# v1-1-0c.net
KiCad netlist of a schematic drawn in EAGLE
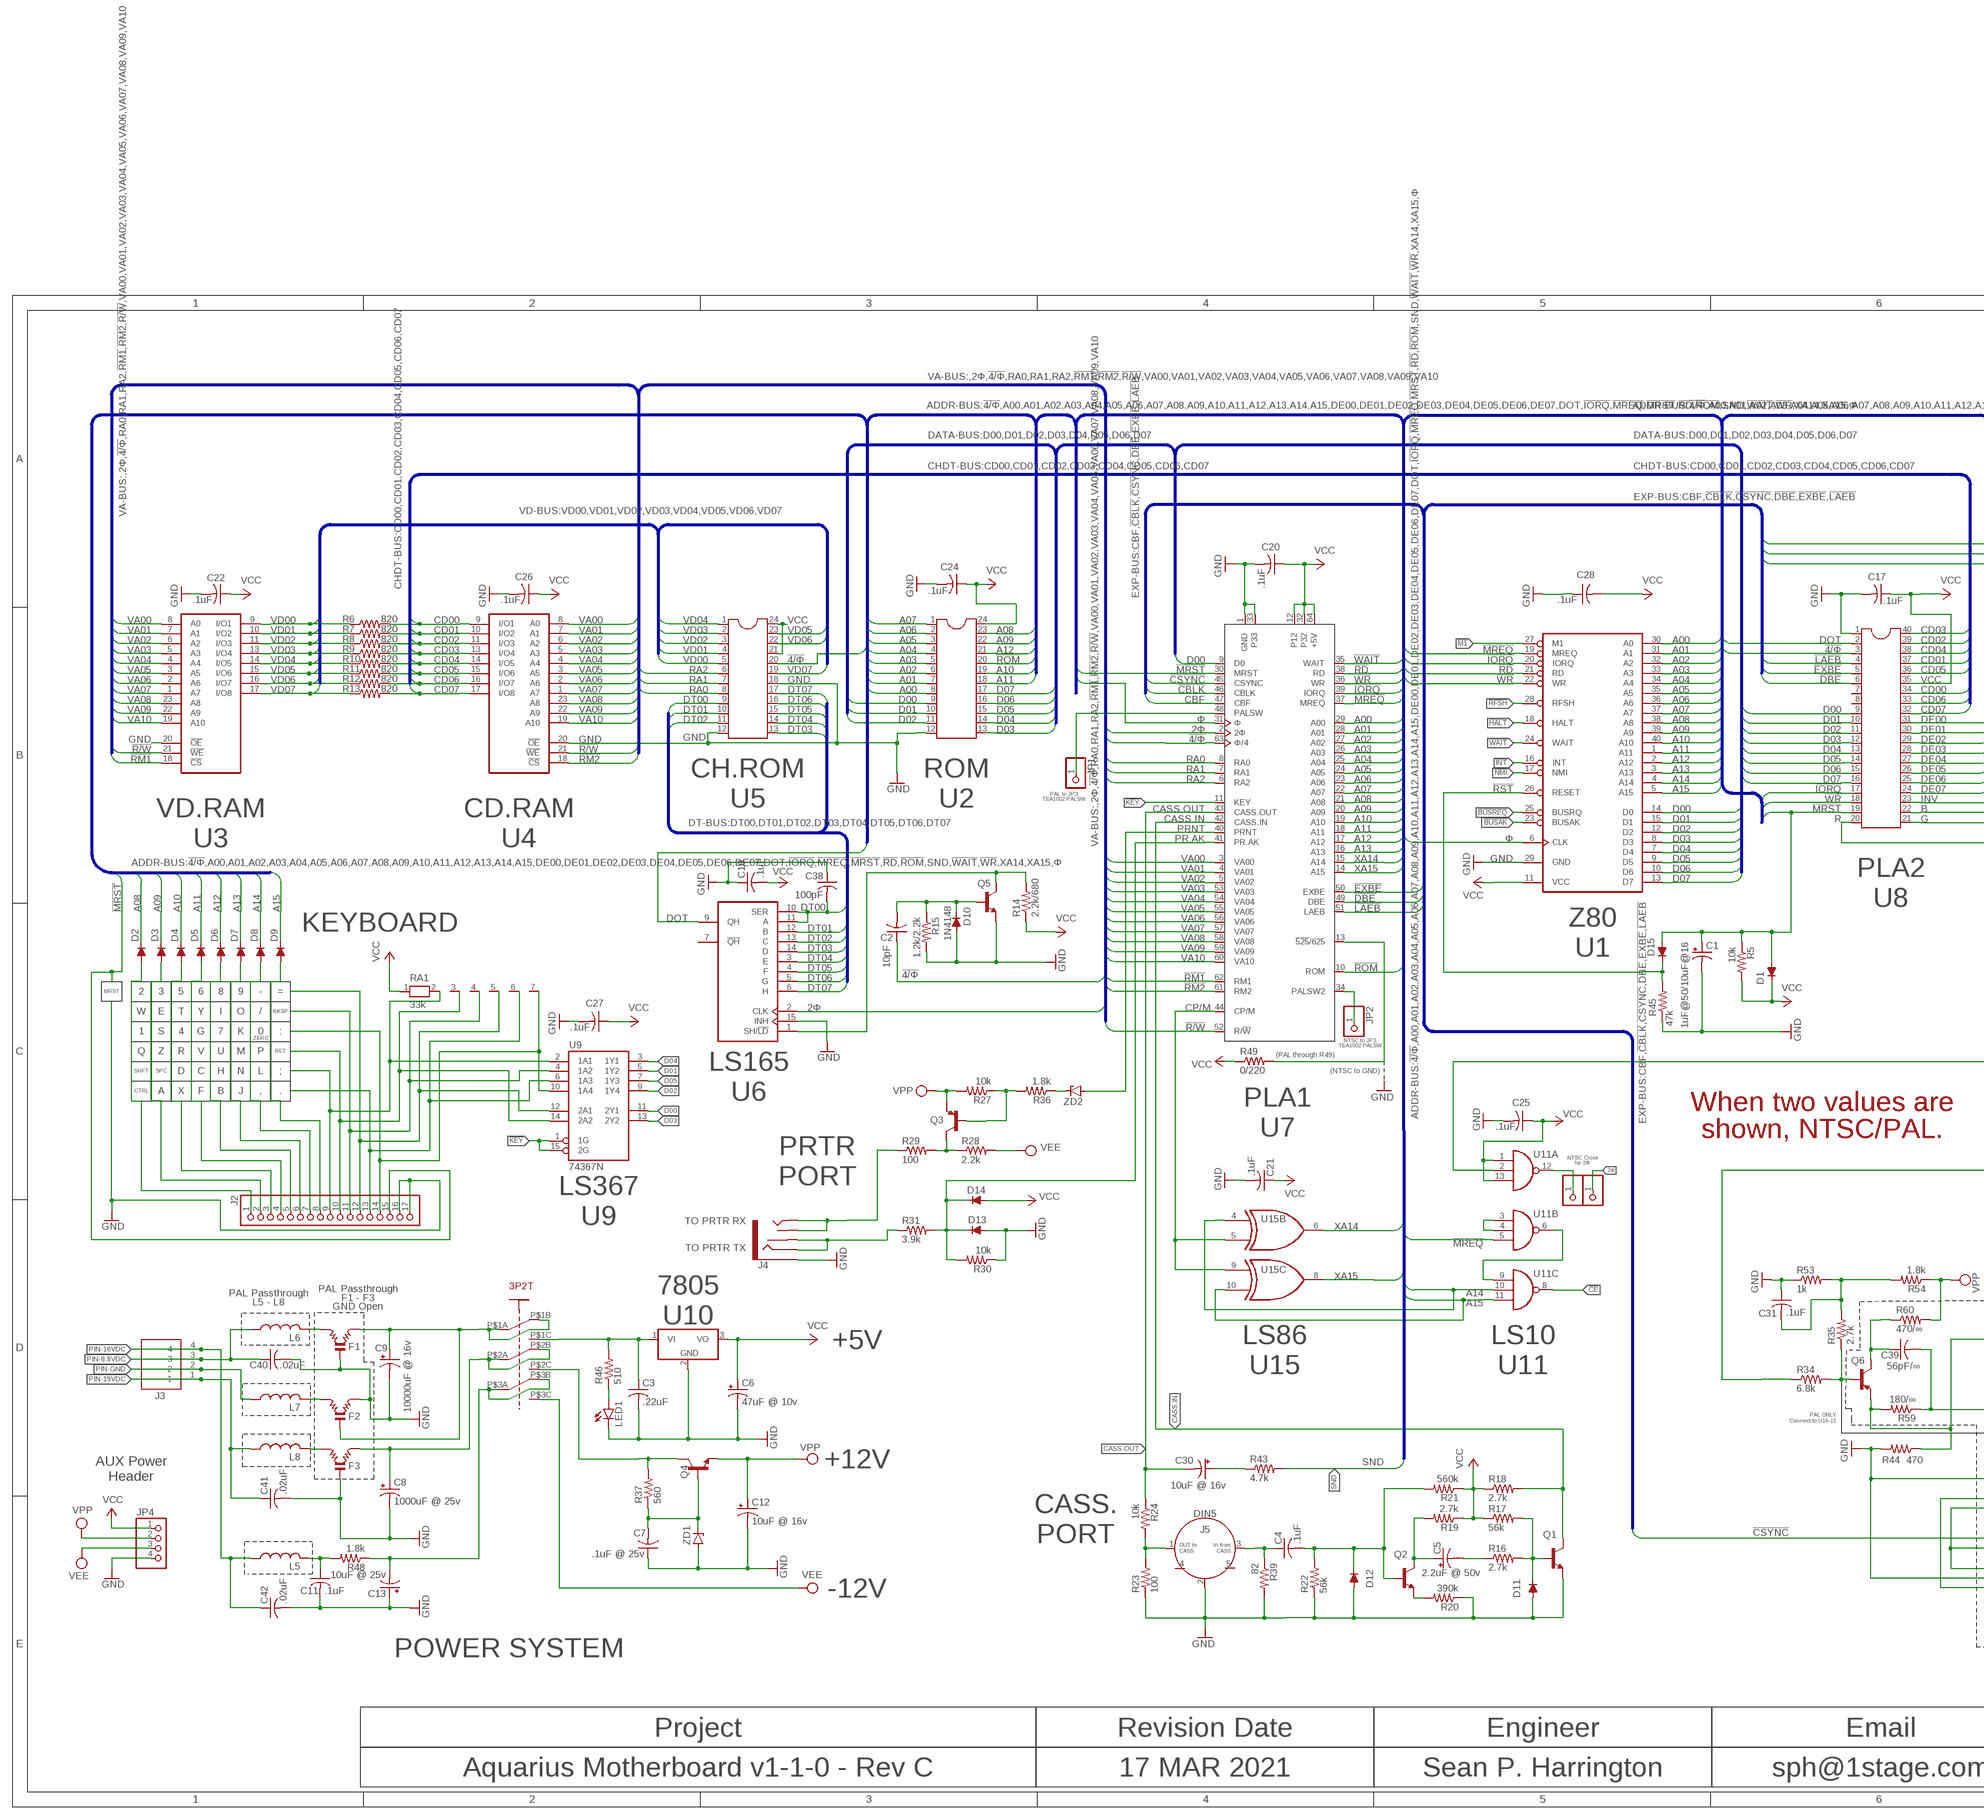
[diagram p0: schematic, sheet 1, part 1 of 2]
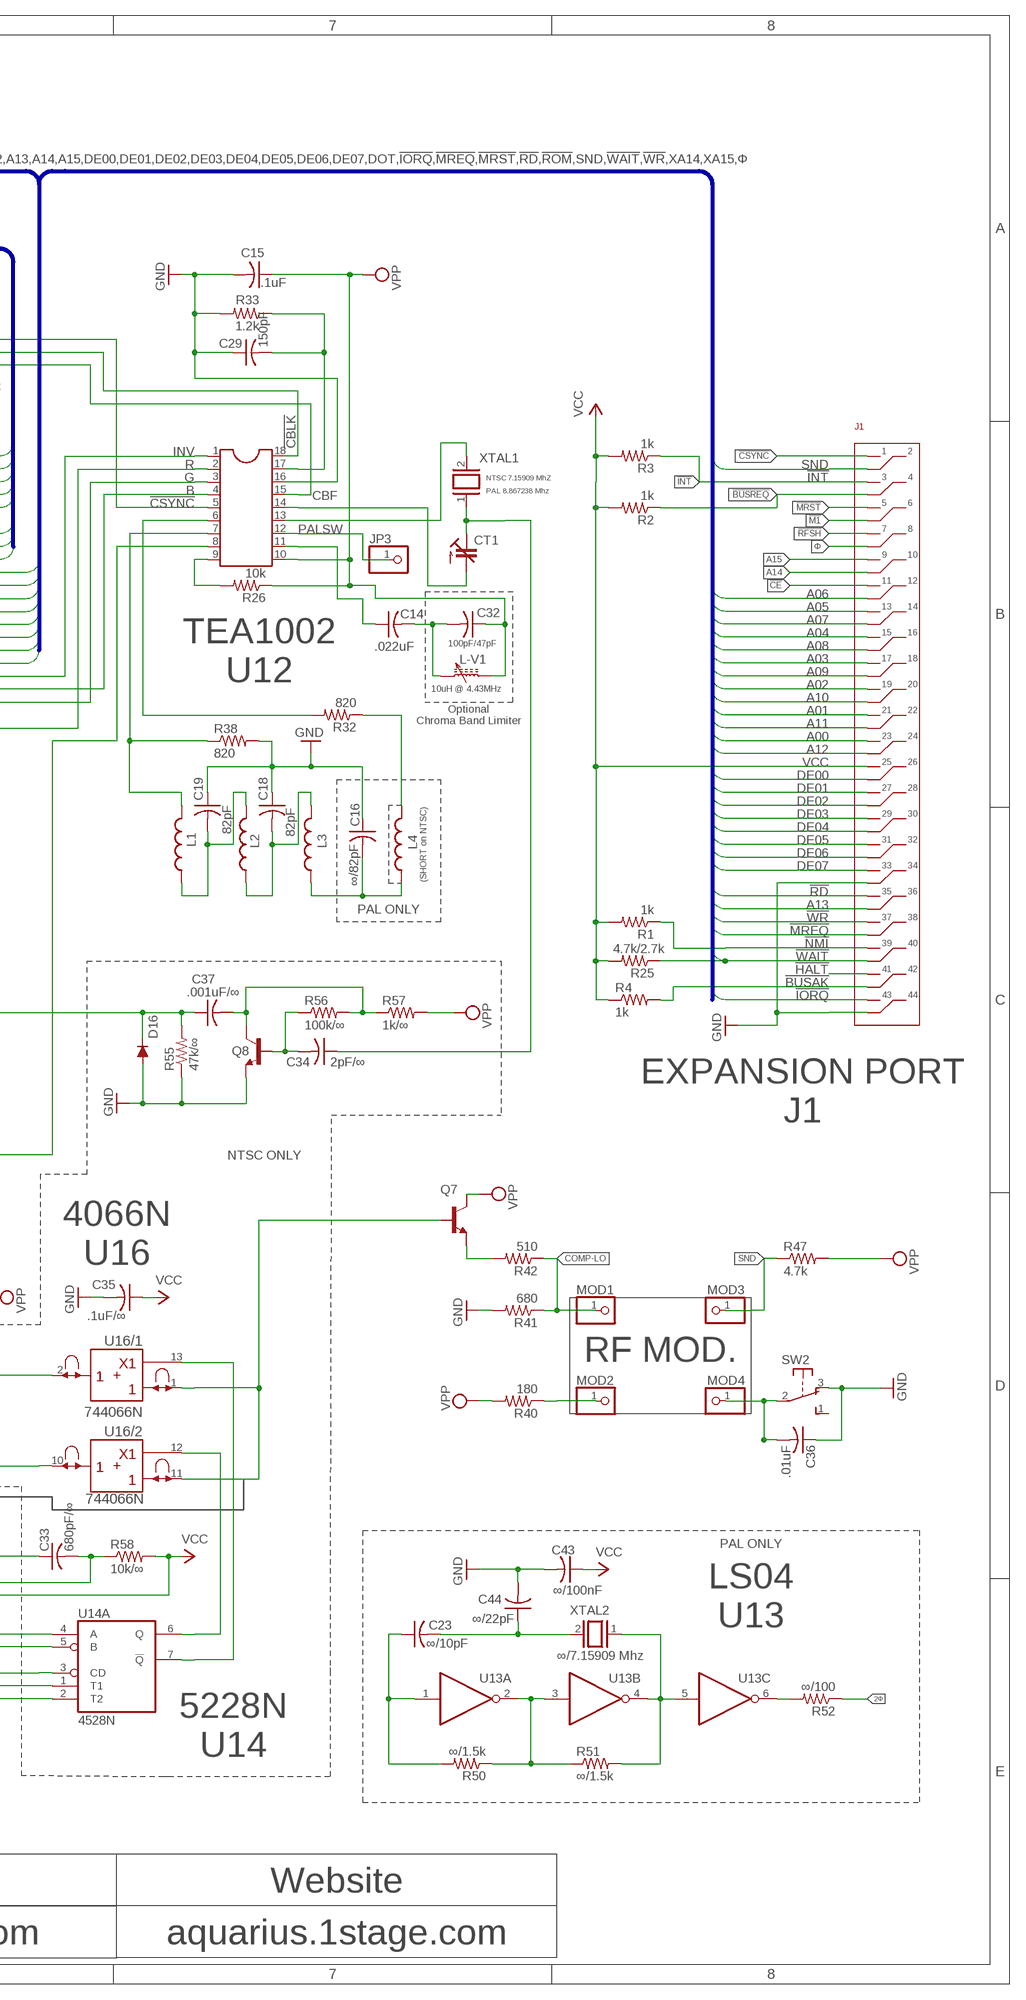
[diagram p1: schematic, sheet 1, part 2 of 2]

(export (version "E")
  (design (tool "Eeschema 10.0.6"))
  (components
    (comp (ref "C1")
      (value "1uF@50/10uF@16")
      (footprint "eagle-import:E2,5-6")
      (libsource (lib "eagle-import") (part "CPOL-USE2.5-6"))
    )
    (comp (ref "C2")
      (value "10pF")
      (footprint "eagle-import:C050-024X044")
      (libsource (lib "eagle-import") (part "C-US050-024X044"))
    )
    (comp (ref "C3")
      (value ".22uF")
      (footprint "eagle-import:C050-025X090")
      (libsource (lib "eagle-import") (part "C-US050-025X090"))
    )
    (comp (ref "C4")
      (value ".1uF")
      (footprint "eagle-import:C050-025X090")
      (libsource (lib "eagle-import") (part "C-US050-025X090"))
    )
    (comp (ref "C5")
      (value "2.2uF @ 50v")
      (footprint "eagle-import:E2,5-6")
      (libsource (lib "eagle-import") (part "CPOL-USE2.5-6"))
    )
    (comp (ref "C6")
      (value "47uF @ 10v")
      (footprint "eagle-import:E2,5-6")
      (libsource (lib "eagle-import") (part "CPOL-USE2.5-6"))
    )
    (comp (ref "C7")
      (value ".1uF @ 25v")
      (footprint "eagle-import:C050-025X090")
      (libsource (lib "eagle-import") (part "C-US050-025X090"))
    )
    (comp (ref "C8")
      (value "1000uF @ 25v")
      (footprint "eagle-import:E7,5-16")
      (libsource (lib "eagle-import") (part "CPOL-USE7.5-16"))
    )
    (comp (ref "C9")
      (value "10000uF @ 16v")
      (footprint "eagle-import:E45-18")
      (libsource (lib "eagle-import") (part "CPOL-USE45-18AXIAL"))
    )
    (comp (ref "C10")
      (value ".1uF")
      (footprint "eagle-import:C050-025X090")
      (libsource (lib "eagle-import") (part "C-US050-025X090"))
    )
    (comp (ref "C11")
      (value ".1uF")
      (footprint "eagle-import:C050-025X090")
      (libsource (lib "eagle-import") (part "C-US050-025X090"))
    )
    (comp (ref "C12")
      (value "10uF @ 16v")
      (footprint "eagle-import:E2,5-6")
      (libsource (lib "eagle-import") (part "CPOL-USE2.5-6"))
    )
    (comp (ref "C13")
      (value "10uF @ 25v")
      (footprint "eagle-import:E2,5-6")
      (libsource (lib "eagle-import") (part "CPOL-USE2.5-6"))
    )
    (comp (ref "C14")
      (value ".022uF")
      (footprint "eagle-import:C050-024X044")
      (libsource (lib "eagle-import") (part "C-US050-024X044"))
    )
    (comp (ref "C15")
      (value ".1uF")
      (footprint "eagle-import:C050-025X090")
      (libsource (lib "eagle-import") (part "C-US050-025X090"))
    )
    (comp (ref "C16")
      (value "∞/82pF")
      (footprint "eagle-import:C050-024X044")
      (libsource (lib "eagle-import") (part "C-US050-024X044"))
    )
    (comp (ref "C17")
      (value ".1uF")
      (footprint "eagle-import:C050-025X090")
      (libsource (lib "eagle-import") (part "C-US050-025X090"))
    )
    (comp (ref "C18")
      (value "82pF")
      (footprint "eagle-import:C050-024X044")
      (libsource (lib "eagle-import") (part "C-US050-024X044"))
    )
    (comp (ref "C19")
      (value "82pF")
      (footprint "eagle-import:C050-024X044")
      (libsource (lib "eagle-import") (part "C-US050-024X044"))
    )
    (comp (ref "C20")
      (value ".1uF")
      (footprint "eagle-import:C050-025X090")
      (libsource (lib "eagle-import") (part "C-US050-025X090"))
    )
    (comp (ref "C21")
      (value ".1uF")
      (footprint "eagle-import:C050-025X090")
      (libsource (lib "eagle-import") (part "C-US050-025X090"))
    )
    (comp (ref "C22")
      (value ".1uF")
      (footprint "eagle-import:C050-025X085")
      (libsource (lib "eagle-import") (part "C-US050-025X085"))
    )
    (comp (ref "C23")
      (value "∞/10pF")
      (footprint "eagle-import:C050-024X044")
      (libsource (lib "eagle-import") (part "C-US050-024X044"))
    )
    (comp (ref "C24")
      (value ".1uF")
      (footprint "eagle-import:C050-025X090")
      (libsource (lib "eagle-import") (part "C-US050-025X090"))
    )
    (comp (ref "C25")
      (value ".1uF")
      (footprint "eagle-import:C050-025X090")
      (libsource (lib "eagle-import") (part "C-US050-025X090"))
    )
    (comp (ref "C26")
      (value ".1uF")
      (footprint "eagle-import:C050-025X085")
      (libsource (lib "eagle-import") (part "C-US050-025X085"))
    )
    (comp (ref "C27")
      (value ".1uF")
      (footprint "eagle-import:C050-025X090")
      (libsource (lib "eagle-import") (part "C-US050-025X090"))
    )
    (comp (ref "C28")
      (value ".1uF")
      (footprint "eagle-import:C050-025X090")
      (libsource (lib "eagle-import") (part "C-US050-025X090"))
    )
    (comp (ref "C29")
      (value "150pF")
      (footprint "eagle-import:C050-024X044")
      (libsource (lib "eagle-import") (part "C-US050-024X044"))
    )
    (comp (ref "C30")
      (value "10uF @ 16v")
      (footprint "eagle-import:E2,5-6")
      (libsource (lib "eagle-import") (part "CPOL-USE2.5-6"))
    )
    (comp (ref "C31")
      (value ".1uF")
      (footprint "eagle-import:C050-024X044")
      (libsource (lib "eagle-import") (part "C-US050-024X044"))
    )
    (comp (ref "C32")
      (value "100pF/47pF")
      (footprint "eagle-import:C025-024X044")
      (libsource (lib "eagle-import") (part "C-US025-024X044"))
    )
    (comp (ref "C33")
      (value "680pF/∞")
      (footprint "eagle-import:C050-024X044")
      (libsource (lib "eagle-import") (part "C-US050-024X044"))
    )
    (comp (ref "C34")
      (value "2pF/∞")
      (footprint "eagle-import:C025-024X044")
      (libsource (lib "eagle-import") (part "C-US025-024X044"))
    )
    (comp (ref "C35")
      (value ".1uF/∞")
      (footprint "eagle-import:C050-025X090")
      (libsource (lib "eagle-import") (part "C-US050-025X090"))
    )
    (comp (ref "C36")
      (value ".01uF")
      (footprint "eagle-import:C050-024X044")
      (libsource (lib "eagle-import") (part "C-US050-024X044"))
    )
    (comp (ref "C37")
      (value ".001uF/∞")
      (footprint "eagle-import:C025-030X050")
      (libsource (lib "eagle-import") (part "C-US025-030X050"))
    )
    (comp (ref "C38")
      (value "100pF")
      (footprint "eagle-import:C050-025X085")
      (libsource (lib "eagle-import") (part "C-US050-025X085"))
    )
    (comp (ref "C39")
      (value "56pF/∞")
      (footprint "eagle-import:C050-024X044")
      (libsource (lib "eagle-import") (part "C-US050-024X044"))
    )
    (comp (ref "C40")
      (value ".02uF")
      (footprint "eagle-import:C050-025X090")
      (libsource (lib "eagle-import") (part "C-US050-025X090"))
    )
    (comp (ref "C41")
      (value ".02uF")
      (footprint "eagle-import:C050-025X090")
      (libsource (lib "eagle-import") (part "C-US050-025X090"))
    )
    (comp (ref "C42")
      (value ".02uF")
      (footprint "eagle-import:C050-025X090")
      (libsource (lib "eagle-import") (part "C-US050-025X090"))
    )
    (comp (ref "C43")
      (value "∞/100nF")
      (footprint "eagle-import:C050-025X090")
      (libsource (lib "eagle-import") (part "C-US050-025X090"))
    )
    (comp (ref "C44")
      (value "∞/22pF")
      (footprint "eagle-import:C050-024X044")
      (libsource (lib "eagle-import") (part "C-US050-024X044"))
    )
    (comp (ref "CT1")
      (value "C-TRIMM808")
      (footprint "eagle-import:CTRIM808-BC")
      (libsource (lib "eagle-import") (part "C-TRIMM808"))
    )
    (comp (ref "D1")
      (value "1N4148")
      (footprint "eagle-import:DO35-10")
      (libsource (lib "eagle-import") (part "1N4148"))
    )
    (comp (ref "D2")
      (value "1N4148H")
      (footprint "eagle-import:DO35-12")
      (libsource (lib "eagle-import") (part "1N4148-12"))
    )
    (comp (ref "D3")
      (value "1N4148H")
      (footprint "eagle-import:DO35-12")
      (libsource (lib "eagle-import") (part "1N4148-12"))
    )
    (comp (ref "D4")
      (value "1N4148H")
      (footprint "eagle-import:DO35-12")
      (libsource (lib "eagle-import") (part "1N4148-12"))
    )
    (comp (ref "D5")
      (value "1N4148H")
      (footprint "eagle-import:DO35-12")
      (libsource (lib "eagle-import") (part "1N4148-12"))
    )
    (comp (ref "D6")
      (value "1N4148H")
      (footprint "eagle-import:DO35-12")
      (libsource (lib "eagle-import") (part "1N4148-12"))
    )
    (comp (ref "D7")
      (value "1N4148H")
      (footprint "eagle-import:DO35-12")
      (libsource (lib "eagle-import") (part "1N4148-12"))
    )
    (comp (ref "D8")
      (value "1N4148H")
      (footprint "eagle-import:DO35-12")
      (libsource (lib "eagle-import") (part "1N4148-12"))
    )
    (comp (ref "D9")
      (value "1N4148H")
      (footprint "eagle-import:DO35-12")
      (libsource (lib "eagle-import") (part "1N4148-12"))
    )
    (comp (ref "D10")
      (value "1N4148")
      (footprint "eagle-import:DO35-10")
      (libsource (lib "eagle-import") (part "1N4148"))
    )
    (comp (ref "D11")
      (value "1N4148")
      (footprint "eagle-import:DO35-10")
      (libsource (lib "eagle-import") (part "1N4148"))
    )
    (comp (ref "D12")
      (value "1N4148")
      (footprint "eagle-import:DO35-10")
      (libsource (lib "eagle-import") (part "1N4148"))
    )
    (comp (ref "D13")
      (value "1N4148")
      (footprint "eagle-import:DO35-10")
      (libsource (lib "eagle-import") (part "1N4148"))
    )
    (comp (ref "D14")
      (value "1N4148")
      (footprint "eagle-import:DO35-10")
      (libsource (lib "eagle-import") (part "1N4148"))
    )
    (comp (ref "D15")
      (value "1N4148")
      (footprint "eagle-import:DO35-10")
      (libsource (lib "eagle-import") (part "1N4148"))
    )
    (comp (ref "D16")
      (value "1N4148")
      (footprint "eagle-import:DO35-10")
      (libsource (lib "eagle-import") (part "1N4148"))
    )
    (comp (ref "F1")
      (value "LCL")
      (footprint "eagle-import:LCL")
      (libsource (lib "eagle-import") (part "LCL"))
    )
    (comp (ref "F2")
      (value "LCL")
      (footprint "eagle-import:LCL")
      (libsource (lib "eagle-import") (part "LCL"))
    )
    (comp (ref "F3")
      (value "LCL")
      (footprint "eagle-import:LCL")
      (libsource (lib "eagle-import") (part "LCL"))
    )
    (comp (ref "J1")
      (value "CR22A-44D-2.54DSA(70)")
      (footprint "eagle-import:CR22A-44D-2.54DSA(70)")
      (libsource (lib "eagle-import") (part "CR22A-44D-2.54DSA(70)"))
    )
    (comp (ref "J2")
      (value "PINHD-1X17")
      (footprint "eagle-import:1X17")
      (libsource (lib "eagle-import") (part "PINHD-1X17"))
    )
    (comp (ref "J3")
      (value "26-60-4040")
      (footprint "eagle-import:SHDR4W155P0X396_1X4_1570X1001X")
      (fields (field (name "MOUSER_PART_NUMBER") "538-26-60-4040"))
      (libsource (lib "eagle-import") (part "26-60-4040"))
    )
    (comp (ref "J4")
      (value "AUDIO_JACK_3.5MM_PTH")
      (footprint "eagle-import:AUDIO-JACK")
      (libsource (lib "eagle-import") (part "AUDIO_JACK_3.5MM_PTH"))
    )
    (comp (ref "J5")
      (value "DIN5")
      (footprint "eagle-import:DIN5-RA-PTH")
      (libsource (lib "eagle-import") (part "DIN5"))
    )
    (comp (ref "JP1")
      (value "PINHD-1X1")
      (footprint "eagle-import:1X01")
      (libsource (lib "eagle-import") (part "PINHD-1X1"))
    )
    (comp (ref "JP2")
      (value "PINHD-1X1")
      (footprint "eagle-import:1X01")
      (libsource (lib "eagle-import") (part "PINHD-1X1"))
    )
    (comp (ref "JP3")
      (value "PINHD-1X1")
      (footprint "eagle-import:1X01")
      (libsource (lib "eagle-import") (part "PINHD-1X1"))
    )
    (comp (ref "JP4")
      (value "PINHD-1X4")
      (footprint "eagle-import:1X04")
      (libsource (lib "eagle-import") (part "PINHD-1X4"))
    )
    (comp (ref "JP5")
      (value "PINHD-1X1")
      (footprint "eagle-import:1X01")
      (libsource (lib "eagle-import") (part "PINHD-1X1"))
    )
    (comp (ref "JP6")
      (value "PINHD-1X1")
      (footprint "eagle-import:1X01")
      (libsource (lib "eagle-import") (part "PINHD-1X1"))
    )
    (comp (ref "L-V1")
      (value "10uH @ 4.43MHz")
      (footprint "eagle-import:10MM-VAR-IND")
      (libsource (lib "eagle-import") (part "L-VAR-IND"))
    )
    (comp (ref "L1")
      (value "L-USTFI0305")
      (footprint "eagle-import:TFI0305")
      (libsource (lib "eagle-import") (part "L-USTFI0305"))
    )
    (comp (ref "L2")
      (value "L-USTFI0305")
      (footprint "eagle-import:TFI0305")
      (libsource (lib "eagle-import") (part "L-USTFI0305"))
    )
    (comp (ref "L3")
      (value "L-USTFI0305")
      (footprint "eagle-import:TFI0305")
      (libsource (lib "eagle-import") (part "L-USTFI0305"))
    )
    (comp (ref "L4")
      (value "L-USTFI0305")
      (footprint "eagle-import:TFI0305")
      (libsource (lib "eagle-import") (part "L-USTFI0305"))
    )
    (comp (ref "L5")
      (value "L-USTFI0305")
      (footprint "eagle-import:TFI0305")
      (libsource (lib "eagle-import") (part "L-USTFI0305"))
    )
    (comp (ref "L6")
      (value "L-USTFI0305")
      (footprint "eagle-import:TFI0305")
      (libsource (lib "eagle-import") (part "L-USTFI0305"))
    )
    (comp (ref "L7")
      (value "L-USTFI0305")
      (footprint "eagle-import:TFI0305")
      (libsource (lib "eagle-import") (part "L-USTFI0305"))
    )
    (comp (ref "L8")
      (value "L-USTFI0305")
      (footprint "eagle-import:TFI0305")
      (libsource (lib "eagle-import") (part "L-USTFI0305"))
    )
    (comp (ref "LED1")
      (value "LED5MM")
      (footprint "eagle-import:LED5MM")
      (libsource (lib "eagle-import") (part "LED5MM"))
    )
    (comp (ref "MOD1")
      (value "PINHD-1X1")
      (footprint "eagle-import:1X01")
      (libsource (lib "eagle-import") (part "PINHD-1X1"))
    )
    (comp (ref "MOD2")
      (value "PINHD-1X1")
      (footprint "eagle-import:1X01")
      (libsource (lib "eagle-import") (part "PINHD-1X1"))
    )
    (comp (ref "MOD3")
      (value "PINHD-1X1")
      (footprint "eagle-import:1X01")
      (libsource (lib "eagle-import") (part "PINHD-1X1"))
    )
    (comp (ref "MOD4")
      (value "PINHD-1X1")
      (footprint "eagle-import:1X01")
      (libsource (lib "eagle-import") (part "PINHD-1X1"))
    )
    (comp (ref "Q1")
      (value "-NPN-TO92-E1")
      (footprint "eagle-import:TO92-E1")
      (libsource (lib "eagle-import") (part "-NPN-TO92-E1"))
    )
    (comp (ref "Q2")
      (value "-NPN-TO92-E1")
      (footprint "eagle-import:TO92-E1")
      (libsource (lib "eagle-import") (part "-NPN-TO92-E1"))
    )
    (comp (ref "Q3")
      (value "-PNP-TO92-E1")
      (footprint "eagle-import:TO92-E1")
      (libsource (lib "eagle-import") (part "-PNP-TO92-E1"))
    )
    (comp (ref "Q4")
      (value "-NPN-TO220V")
      (footprint "eagle-import:TO220V")
      (libsource (lib "eagle-import") (part "transistor_402_-NPN-TO220V"))
    )
    (comp (ref "Q5")
      (value "-NPN-TO92-E1")
      (footprint "eagle-import:TO92-E1")
      (libsource (lib "eagle-import") (part "-NPN-TO92-E1"))
    )
    (comp (ref "Q6")
      (value "-PNP-TO92-E1")
      (footprint "eagle-import:TO92-E1")
      (libsource (lib "eagle-import") (part "-PNP-TO92-E1"))
    )
    (comp (ref "Q7")
      (value "-NPN-TO92-E1")
      (footprint "eagle-import:TO92-E1")
      (libsource (lib "eagle-import") (part "-NPN-TO92-E1"))
    )
    (comp (ref "Q8")
      (value "-NPN-TO92-E1")
      (footprint "eagle-import:TO92-E1")
      (libsource (lib "eagle-import") (part "-NPN-TO92-E1"))
    )
    (comp (ref "R1")
      (value "1k")
      (footprint "eagle-import:0207_10")
      (libsource (lib "eagle-import") (part "R-US_0207/10"))
    )
    (comp (ref "R2")
      (value "1k")
      (footprint "eagle-import:0207_10")
      (libsource (lib "eagle-import") (part "R-US_0207/10"))
    )
    (comp (ref "R3")
      (value "1k")
      (footprint "eagle-import:0207_10")
      (libsource (lib "eagle-import") (part "R-US_0207/10"))
    )
    (comp (ref "R4")
      (value "1k")
      (footprint "eagle-import:0207_10")
      (libsource (lib "eagle-import") (part "R-US_0207/10"))
    )
    (comp (ref "R5")
      (value "10k")
      (footprint "eagle-import:0207_10")
      (libsource (lib "eagle-import") (part "R-US_0207/10"))
    )
    (comp (ref "R6")
      (value "820")
      (footprint "eagle-import:0207_10")
      (libsource (lib "eagle-import") (part "R-US_0207/10"))
    )
    (comp (ref "R7")
      (value "820")
      (footprint "eagle-import:0207_10")
      (libsource (lib "eagle-import") (part "R-US_0207/10"))
    )
    (comp (ref "R8")
      (value "820")
      (footprint "eagle-import:0207_10")
      (libsource (lib "eagle-import") (part "R-US_0207/10"))
    )
    (comp (ref "R9")
      (value "820")
      (footprint "eagle-import:0207_10")
      (libsource (lib "eagle-import") (part "R-US_0207/10"))
    )
    (comp (ref "R10")
      (value "820")
      (footprint "eagle-import:0207_10")
      (libsource (lib "eagle-import") (part "R-US_0207/10"))
    )
    (comp (ref "R11")
      (value "820")
      (footprint "eagle-import:0207_10")
      (libsource (lib "eagle-import") (part "R-US_0207/10"))
    )
    (comp (ref "R12")
      (value "820")
      (footprint "eagle-import:0207_10")
      (libsource (lib "eagle-import") (part "R-US_0207/10"))
    )
    (comp (ref "R13")
      (value "820")
      (footprint "eagle-import:0207_10")
      (libsource (lib "eagle-import") (part "R-US_0207/10"))
    )
    (comp (ref "R14")
      (value "2.2k/680")
      (footprint "eagle-import:0207_10")
      (libsource (lib "eagle-import") (part "R-US_0207/10"))
    )
    (comp (ref "R15")
      (value "1.2k/2.2k")
      (footprint "eagle-import:0207_10")
      (libsource (lib "eagle-import") (part "R-US_0207/10"))
    )
    (comp (ref "R16")
      (value "2.7k")
      (footprint "eagle-import:0207_10")
      (libsource (lib "eagle-import") (part "R-US_0207/10"))
    )
    (comp (ref "R17")
      (value "56k")
      (footprint "eagle-import:0207_10")
      (libsource (lib "eagle-import") (part "R-US_0207/10"))
    )
    (comp (ref "R18")
      (value "2.7k")
      (footprint "eagle-import:0207_10")
      (libsource (lib "eagle-import") (part "R-US_0207/10"))
    )
    (comp (ref "R19")
      (value "2.7k")
      (footprint "eagle-import:0207_10")
      (libsource (lib "eagle-import") (part "R-US_0207/10"))
    )
    (comp (ref "R20")
      (value "390k")
      (footprint "eagle-import:0207_10")
      (libsource (lib "eagle-import") (part "R-US_0207/10"))
    )
    (comp (ref "R21")
      (value "560k")
      (footprint "eagle-import:0207_10")
      (libsource (lib "eagle-import") (part "R-US_0207/10"))
    )
    (comp (ref "R22")
      (value "56k")
      (footprint "eagle-import:0207_10")
      (libsource (lib "eagle-import") (part "R-US_0207/10"))
    )
    (comp (ref "R23")
      (value "100")
      (footprint "eagle-import:0207_10")
      (libsource (lib "eagle-import") (part "R-US_0207/10"))
    )
    (comp (ref "R24")
      (value "10k")
      (footprint "eagle-import:0207_10")
      (libsource (lib "eagle-import") (part "R-US_0207/10"))
    )
    (comp (ref "R25")
      (value "4.7k/2.7k")
      (footprint "eagle-import:0207_10")
      (libsource (lib "eagle-import") (part "R-US_0207/10"))
    )
    (comp (ref "R26")
      (value "10k")
      (footprint "eagle-import:0207_10")
      (libsource (lib "eagle-import") (part "R-US_0207/10"))
    )
    (comp (ref "R27")
      (value "10k")
      (footprint "eagle-import:0207_10")
      (libsource (lib "eagle-import") (part "R-US_0207/10"))
    )
    (comp (ref "R28")
      (value "2.2k")
      (footprint "eagle-import:0207_10")
      (libsource (lib "eagle-import") (part "R-US_0207/10"))
    )
    (comp (ref "R29")
      (value "100")
      (footprint "eagle-import:0207_10")
      (libsource (lib "eagle-import") (part "R-US_0207/10"))
    )
    (comp (ref "R30")
      (value "10k")
      (footprint "eagle-import:0207_10")
      (libsource (lib "eagle-import") (part "R-US_0207/10"))
    )
    (comp (ref "R31")
      (value "3.9k")
      (footprint "eagle-import:0207_10")
      (libsource (lib "eagle-import") (part "R-US_0207/10"))
    )
    (comp (ref "R32")
      (value "820")
      (footprint "eagle-import:0207_10")
      (libsource (lib "eagle-import") (part "R-US_0207/10"))
    )
    (comp (ref "R33")
      (value "1.2k")
      (footprint "eagle-import:0207_10")
      (libsource (lib "eagle-import") (part "R-US_0207/10"))
    )
    (comp (ref "R34")
      (value "6.8k")
      (footprint "eagle-import:0207_10")
      (libsource (lib "eagle-import") (part "R-US_0207/10"))
    )
    (comp (ref "R35")
      (value "2.7k")
      (footprint "eagle-import:0207_10")
      (libsource (lib "eagle-import") (part "R-US_0207/10"))
    )
    (comp (ref "R36")
      (value "1.8k")
      (footprint "eagle-import:0207_10")
      (libsource (lib "eagle-import") (part "R-US_0207/10"))
    )
    (comp (ref "R37")
      (value "560")
      (footprint "eagle-import:0207_10")
      (libsource (lib "eagle-import") (part "R-US_0207/10"))
    )
    (comp (ref "R38")
      (value "820")
      (footprint "eagle-import:0207_10")
      (libsource (lib "eagle-import") (part "R-US_0207/10"))
    )
    (comp (ref "R39")
      (value "82")
      (footprint "eagle-import:0207_10")
      (libsource (lib "eagle-import") (part "R-US_0207/10"))
    )
    (comp (ref "R40")
      (value "180")
      (footprint "eagle-import:0207_10")
      (libsource (lib "eagle-import") (part "R-US_0207/10"))
    )
    (comp (ref "R41")
      (value "680")
      (footprint "eagle-import:0207_10")
      (libsource (lib "eagle-import") (part "R-US_0207/10"))
    )
    (comp (ref "R42")
      (value "510")
      (footprint "eagle-import:0207_10")
      (libsource (lib "eagle-import") (part "R-US_0207/10"))
    )
    (comp (ref "R43")
      (value "4.7k")
      (footprint "eagle-import:0207_10")
      (libsource (lib "eagle-import") (part "R-US_0207/10"))
    )
    (comp (ref "R44")
      (value "470")
      (footprint "eagle-import:0207_10")
      (libsource (lib "eagle-import") (part "R-US_0207/10"))
    )
    (comp (ref "R45")
      (value "47k")
      (footprint "eagle-import:0207_10")
      (libsource (lib "eagle-import") (part "R-US_0207/10"))
    )
    (comp (ref "R46")
      (value "510")
      (footprint "eagle-import:0207_10")
      (libsource (lib "eagle-import") (part "R-US_0207/10"))
    )
    (comp (ref "R47")
      (value "4.7k")
      (footprint "eagle-import:0207_10")
      (libsource (lib "eagle-import") (part "R-US_0207/10"))
    )
    (comp (ref "R48")
      (value "1.8k")
      (footprint "eagle-import:0207_10")
      (libsource (lib "eagle-import") (part "R-US_0207/10"))
    )
    (comp (ref "R49")
      (value "0/220")
      (footprint "eagle-import:0207_10")
      (libsource (lib "eagle-import") (part "R-US_0207/10"))
    )
    (comp (ref "R50")
      (value "∞/1.5k")
      (footprint "eagle-import:0207_10")
      (libsource (lib "eagle-import") (part "R-US_0207/10"))
    )
    (comp (ref "R51")
      (value "∞/1.5k")
      (footprint "eagle-import:0207_10")
      (libsource (lib "eagle-import") (part "R-US_0207/10"))
    )
    (comp (ref "R52")
      (value "∞/100")
      (footprint "eagle-import:0207_10")
      (libsource (lib "eagle-import") (part "R-US_0207/10"))
    )
    (comp (ref "R53")
      (value "1k")
      (footprint "eagle-import:0207_10")
      (libsource (lib "eagle-import") (part "R-US_0207/10"))
    )
    (comp (ref "R54")
      (value "1.8k")
      (footprint "eagle-import:0207_10")
      (libsource (lib "eagle-import") (part "R-US_0207/10"))
    )
    (comp (ref "R55")
      (value "47k/∞")
      (footprint "eagle-import:0207_10")
      (libsource (lib "eagle-import") (part "R-US_0207/10"))
    )
    (comp (ref "R56")
      (value "100k/∞")
      (footprint "eagle-import:0207_10")
      (libsource (lib "eagle-import") (part "R-US_0207/10"))
    )
    (comp (ref "R57")
      (value "1k/∞")
      (footprint "eagle-import:0207_10")
      (libsource (lib "eagle-import") (part "R-US_0207/10"))
    )
    (comp (ref "R58")
      (value "10k/∞")
      (footprint "eagle-import:0207_10")
      (libsource (lib "eagle-import") (part "R-US_0207/10"))
    )
    (comp (ref "R59")
      (value "180/∞")
      (footprint "eagle-import:0207_10")
      (libsource (lib "eagle-import") (part "R-US_0207/10"))
    )
    (comp (ref "R60")
      (value "470/∞")
      (footprint "eagle-import:0207_10")
      (libsource (lib "eagle-import") (part "R-US_0207/10"))
    )
    (comp (ref "RA1")
      (value "33k")
      (footprint "eagle-import:RN-7")
      (libsource (lib "eagle-import") (part "RN06"))
    )
    (comp (ref "SW1")
      (value "3PDT-AQ-SWITCH")
      (footprint "eagle-import:3PDT-AQ-SWITCH")
      (libsource (lib "eagle-import") (part "3PDT-AQ-SWITCH"))
    )
    (comp (ref "SW2")
      (value "9077-1")
      (footprint "eagle-import:9077-1")
      (libsource (lib "eagle-import") (part "9077-1"))
    )
    (comp (ref "U1")
      (value "Z80CPU")
      (footprint "eagle-import:DIL40")
      (libsource (lib "eagle-import") (part "Z80CPU"))
    )
    (comp (ref "U2")
      (value "DIL24-6")
      (footprint "eagle-import:DIL24-6")
      (libsource (lib "eagle-import") (part "DIL24-6"))
    )
    (comp (ref "U3")
      (value "6116P")
      (footprint "eagle-import:DIL24-6")
      (libsource (lib "eagle-import") (part "6116P"))
    )
    (comp (ref "U4")
      (value "6116P")
      (footprint "eagle-import:DIL24-6")
      (libsource (lib "eagle-import") (part "6116P"))
    )
    (comp (ref "U5")
      (value "DIL24-6")
      (footprint "eagle-import:DIL24-6")
      (libsource (lib "eagle-import") (part "DIL24-6"))
    )
    (comp (ref "U6")
      (value "74LS165N")
      (footprint "eagle-import:DIL16")
      (libsource (lib "eagle-import") (part "74165NLS"))
    )
    (comp (ref "U7")
      (value "HD61K202P-PLA1")
      (footprint "eagle-import:HD61K202P-PLA1")
      (libsource (lib "eagle-import") (part "HD61K202P-PLA1"))
    )
    (comp (ref "U8")
      (value "DIL40")
      (footprint "eagle-import:DIL40")
      (libsource (lib "eagle-import") (part "DIL40"))
    )
    (comp (ref "U9")
      (value "74367N")
      (footprint "eagle-import:DIL16")
      (libsource (lib "eagle-import") (part "74367N"))
    )
    (comp (ref "U10")
      (value "7805")
      (footprint "eagle-import:TO220V")
      (libsource (lib "eagle-import") (part "78TV05"))
    )
    (comp (ref "U11")
      (value "74LS10N")
      (footprint "eagle-import:DIL14")
      (libsource (lib "eagle-import") (part "7410NLS"))
    )
    (comp (ref "U12")
      (value "DIL18")
      (footprint "eagle-import:DIL18")
      (libsource (lib "eagle-import") (part "DIL18"))
    )
    (comp (ref "U13")
      (value "74LS04N")
      (footprint "eagle-import:DIL14")
      (libsource (lib "eagle-import") (part "7404NLS"))
    )
    (comp (ref "U14")
      (value "4528N")
      (footprint "eagle-import:DIL16")
      (libsource (lib "eagle-import") (part "4528N"))
    )
    (comp (ref "U15")
      (value "74LS86N")
      (footprint "eagle-import:DIL14")
      (libsource (lib "eagle-import") (part "7486NLS"))
    )
    (comp (ref "U16")
      (value "744066N")
      (footprint "eagle-import:DIL14")
      (libsource (lib "eagle-import") (part "744066N"))
    )
    (comp (ref "XTAL1")
      (value "7.15909 MhZ")
      (footprint "eagle-import:Q")
      (libsource (lib "eagle-import") (part "special_367_XTAL"))
    )
    (comp (ref "XTAL2")
      (value "∞/7.15909 Mhz")
      (footprint "eagle-import:Q")
      (libsource (lib "eagle-import") (part "XTAL"))
    )
    (comp (ref "ZD1")
      (value "ZENER-DIODEZD-10")
      (footprint "eagle-import:ZDIO-10")
      (libsource (lib "eagle-import") (part "ZENER-DIODEZD-10"))
    )
    (comp (ref "ZD2")
      (value "ZENER-DIODEZD-7.5")
      (footprint "eagle-import:ZDIO-7.5")
      (libsource (lib "eagle-import") (part "ZENER-DIODEZD-7.5"))
    )
  )
  (nets
    (net (code "8") (name "/A00") (class "Default")
      (node (ref "J1") (pin "P$23") (pinfunction "X23_P$23") (pintype "bidirectional"))
      (node (ref "U1") (pin "30") (pinfunction "A0_30") (pintype "output"))
      (node (ref "U2") (pin "8") (pinfunction "8_8") (pintype "passive"))
      (node (ref "U7") (pin "29") (pinfunction "A00_29") (pintype "bidirectional"))
    )
    (net (code "9") (name "/A01") (class "Default")
      (node (ref "J1") (pin "P$21") (pinfunction "X21_P$21") (pintype "bidirectional"))
      (node (ref "U1") (pin "31") (pinfunction "A1_31") (pintype "output"))
      (node (ref "U2") (pin "7") (pinfunction "7_7") (pintype "passive"))
      (node (ref "U7") (pin "28") (pinfunction "A01_28") (pintype "bidirectional"))
    )
    (net (code "10") (name "/A02") (class "Default")
      (node (ref "J1") (pin "P$19") (pinfunction "X19_P$19") (pintype "bidirectional"))
      (node (ref "U1") (pin "32") (pinfunction "A2_32") (pintype "output"))
      (node (ref "U2") (pin "6") (pinfunction "6_6") (pintype "passive"))
      (node (ref "U7") (pin "27") (pinfunction "A02_27") (pintype "bidirectional"))
    )
    (net (code "11") (name "/A03") (class "Default")
      (node (ref "J1") (pin "P$17") (pinfunction "X17_P$17") (pintype "bidirectional"))
      (node (ref "U1") (pin "33") (pinfunction "A3_33") (pintype "output"))
      (node (ref "U2") (pin "5") (pinfunction "5_5") (pintype "passive"))
      (node (ref "U7") (pin "26") (pinfunction "A03_26") (pintype "bidirectional"))
    )
    (net (code "12") (name "/A04") (class "Default")
      (node (ref "J1") (pin "P$15") (pinfunction "X15_P$15") (pintype "bidirectional"))
      (node (ref "U1") (pin "34") (pinfunction "A4_34") (pintype "output"))
      (node (ref "U2") (pin "4") (pinfunction "4_4") (pintype "passive"))
      (node (ref "U7") (pin "25") (pinfunction "A04_25") (pintype "bidirectional"))
    )
    (net (code "13") (name "/A05") (class "Default")
      (node (ref "J1") (pin "P$13") (pinfunction "X13_P$13") (pintype "bidirectional"))
      (node (ref "U1") (pin "35") (pinfunction "A5_35") (pintype "output"))
      (node (ref "U2") (pin "3") (pinfunction "3_3") (pintype "passive"))
      (node (ref "U7") (pin "24") (pinfunction "A05_24") (pintype "bidirectional"))
    )
    (net (code "14") (name "/A06") (class "Default")
      (node (ref "J1") (pin "P$12") (pinfunction "X12_P$12") (pintype "bidirectional"))
      (node (ref "U1") (pin "36") (pinfunction "A6_36") (pintype "output"))
      (node (ref "U2") (pin "2") (pinfunction "2_2") (pintype "passive"))
      (node (ref "U7") (pin "23") (pinfunction "A06_23") (pintype "bidirectional"))
    )
    (net (code "15") (name "/A07") (class "Default")
      (node (ref "J1") (pin "P$14") (pinfunction "X14_P$14") (pintype "bidirectional"))
      (node (ref "U1") (pin "37") (pinfunction "A7_37") (pintype "output"))
      (node (ref "U2") (pin "1") (pinfunction "1_1") (pintype "passive"))
      (node (ref "U7") (pin "22") (pinfunction "A07_22") (pintype "bidirectional"))
    )
    (net (code "16") (name "/A08") (class "Default")
      (node (ref "D2") (pin "C") (pinfunction "C_C") (pintype "passive"))
      (node (ref "J1") (pin "P$16") (pinfunction "X16_P$16") (pintype "bidirectional"))
      (node (ref "U1") (pin "38") (pinfunction "A8_38") (pintype "output"))
      (node (ref "U2") (pin "23") (pinfunction "23_23") (pintype "passive"))
      (node (ref "U7") (pin "21") (pinfunction "A08_21") (pintype "bidirectional"))
    )
    (net (code "17") (name "/A09") (class "Default")
      (node (ref "D3") (pin "C") (pinfunction "C_C") (pintype "passive"))
      (node (ref "J1") (pin "P$18") (pinfunction "X18_P$18") (pintype "bidirectional"))
      (node (ref "U1") (pin "39") (pinfunction "A9_39") (pintype "output"))
      (node (ref "U2") (pin "22") (pinfunction "22_22") (pintype "passive"))
      (node (ref "U7") (pin "20") (pinfunction "A09_20") (pintype "bidirectional"))
    )
    (net (code "18") (name "/A10") (class "Default")
      (node (ref "D4") (pin "C") (pinfunction "C_C") (pintype "passive"))
      (node (ref "J1") (pin "P$20") (pinfunction "X20_P$20") (pintype "bidirectional"))
      (node (ref "U1") (pin "40") (pinfunction "A10_40") (pintype "output"))
      (node (ref "U2") (pin "19") (pinfunction "19_19") (pintype "passive"))
      (node (ref "U7") (pin "19") (pinfunction "A10_19") (pintype "bidirectional"))
    )
    (net (code "19") (name "/A11") (class "Default")
      (node (ref "D5") (pin "C") (pinfunction "C_C") (pintype "passive"))
      (node (ref "J1") (pin "P$22") (pinfunction "X22_P$22") (pintype "bidirectional"))
      (node (ref "U1") (pin "1") (pinfunction "A11_1") (pintype "output"))
      (node (ref "U2") (pin "18") (pinfunction "18_18") (pintype "passive"))
      (node (ref "U7") (pin "18") (pinfunction "A11_18") (pintype "bidirectional"))
    )
    (net (code "20") (name "/A12") (class "Default")
      (node (ref "D6") (pin "C") (pinfunction "C_C") (pintype "passive"))
      (node (ref "J1") (pin "P$24") (pinfunction "X24_P$24") (pintype "bidirectional"))
      (node (ref "U1") (pin "2") (pinfunction "A12_2") (pintype "output"))
      (node (ref "U2") (pin "21") (pinfunction "21_21") (pintype "passive"))
      (node (ref "U7") (pin "17") (pinfunction "A12_17") (pintype "bidirectional"))
    )
    (net (code "21") (name "/A13") (class "Default")
      (node (ref "D7") (pin "C") (pinfunction "C_C") (pintype "passive"))
      (node (ref "J1") (pin "P$36") (pinfunction "X36_P$36") (pintype "bidirectional"))
      (node (ref "U1") (pin "3") (pinfunction "A13_3") (pintype "output"))
      (node (ref "U7") (pin "16") (pinfunction "A13_16") (pintype "bidirectional"))
    )
    (net (code "22") (name "/B") (class "Default")
      (node (ref "U12") (pin "4") (pinfunction "4_4") (pintype "passive"))
      (node (ref "U8") (pin "22") (pinfunction "22_22") (pintype "passive"))
    )
    (net (code "23") (name "/CBF") (class "Default")
      (node (ref "U12") (pin "15") (pinfunction "15_15") (pintype "passive"))
      (node (ref "U7") (pin "47") (pinfunction "CBF_47") (pintype "bidirectional"))
    )
    (net (code "24") (name "/CD00") (class "Default")
      (node (ref "R6") (pin "2") (pinfunction "2_2") (pintype "passive"))
      (node (ref "U4") (pin "9") (pinfunction "I/O1_9") (pintype "bidirectional"))
      (node (ref "U8") (pin "34") (pinfunction "34_34") (pintype "passive"))
    )
    (net (code "25") (name "/CD01") (class "Default")
      (node (ref "R7") (pin "2") (pinfunction "2_2") (pintype "passive"))
      (node (ref "U4") (pin "10") (pinfunction "I/O2_10") (pintype "bidirectional"))
      (node (ref "U8") (pin "37") (pinfunction "37_37") (pintype "passive"))
    )
    (net (code "26") (name "/CD02") (class "Default")
      (node (ref "R8") (pin "2") (pinfunction "2_2") (pintype "passive"))
      (node (ref "U4") (pin "11") (pinfunction "I/O3_11") (pintype "bidirectional"))
      (node (ref "U8") (pin "39") (pinfunction "39_39") (pintype "passive"))
    )
    (net (code "27") (name "/CD03") (class "Default")
      (node (ref "R9") (pin "2") (pinfunction "2_2") (pintype "passive"))
      (node (ref "U4") (pin "13") (pinfunction "I/O4_13") (pintype "bidirectional"))
      (node (ref "U8") (pin "40") (pinfunction "40_40") (pintype "passive"))
    )
    (net (code "28") (name "/CD04") (class "Default")
      (node (ref "R10") (pin "2") (pinfunction "2_2") (pintype "passive"))
      (node (ref "U4") (pin "14") (pinfunction "I/O5_14") (pintype "bidirectional"))
      (node (ref "U8") (pin "38") (pinfunction "38_38") (pintype "passive"))
    )
    (net (code "29") (name "/CD05") (class "Default")
      (node (ref "R11") (pin "2") (pinfunction "2_2") (pintype "passive"))
      (node (ref "U4") (pin "15") (pinfunction "I/O6_15") (pintype "bidirectional"))
      (node (ref "U8") (pin "36") (pinfunction "36_36") (pintype "passive"))
    )
    (net (code "30") (name "/CD06") (class "Default")
      (node (ref "R12") (pin "2") (pinfunction "2_2") (pintype "passive"))
      (node (ref "U4") (pin "16") (pinfunction "I/O7_16") (pintype "bidirectional"))
      (node (ref "U8") (pin "33") (pinfunction "33_33") (pintype "passive"))
    )
    (net (code "31") (name "/CD07") (class "Default")
      (node (ref "R13") (pin "2") (pinfunction "2_2") (pintype "passive"))
      (node (ref "U4") (pin "17") (pinfunction "I/O8_17") (pintype "bidirectional"))
      (node (ref "U8") (pin "32") (pinfunction "32_32") (pintype "passive"))
    )
    (net (code "32") (name "/CP{slash}M") (class "Default")
      (node (ref "U15") (pin "5") (pinfunction "I1_5") (pintype "input"))
      (node (ref "U15") (pin "9") (pinfunction "I0_9") (pintype "input"))
      (node (ref "U7") (pin "44") (pinfunction "CP/M_44") (pintype "bidirectional"))
    )
    (net (code "33") (name "/D06") (class "Default")
      (node (ref "U1") (pin "10") (pinfunction "D6_10") (pintype "bidirectional"))
      (node (ref "U2") (pin "16") (pinfunction "16_16") (pintype "passive"))
      (node (ref "U8") (pin "15") (pinfunction "15_15") (pintype "passive"))
    )
    (net (code "34") (name "/D07") (class "Default")
      (node (ref "U1") (pin "13") (pinfunction "D7_13") (pintype "bidirectional"))
      (node (ref "U2") (pin "17") (pinfunction "17_17") (pintype "passive"))
      (node (ref "U8") (pin "16") (pinfunction "16_16") (pintype "passive"))
    )
    (net (code "35") (name "/DE00") (class "Default")
      (node (ref "J1") (pin "P$26") (pinfunction "X26_P$26") (pintype "bidirectional"))
      (node (ref "U8") (pin "31") (pinfunction "31_31") (pintype "passive"))
    )
    (net (code "36") (name "/DE01") (class "Default")
      (node (ref "J1") (pin "P$27") (pinfunction "X27_P$27") (pintype "bidirectional"))
      (node (ref "U8") (pin "30") (pinfunction "30_30") (pintype "passive"))
    )
    (net (code "37") (name "/DE02") (class "Default")
      (node (ref "J1") (pin "P$28") (pinfunction "X28_P$28") (pintype "bidirectional"))
      (node (ref "U8") (pin "29") (pinfunction "29_29") (pintype "passive"))
    )
    (net (code "38") (name "/DE03") (class "Default")
      (node (ref "J1") (pin "P$29") (pinfunction "X29_P$29") (pintype "bidirectional"))
      (node (ref "U8") (pin "28") (pinfunction "28_28") (pintype "passive"))
    )
    (net (code "39") (name "/DE04") (class "Default")
      (node (ref "J1") (pin "P$30") (pinfunction "X30_P$30") (pintype "bidirectional"))
      (node (ref "U8") (pin "27") (pinfunction "27_27") (pintype "passive"))
    )
    (net (code "40") (name "/DE05") (class "Default")
      (node (ref "J1") (pin "P$31") (pinfunction "X31_P$31") (pintype "bidirectional"))
      (node (ref "U8") (pin "26") (pinfunction "26_26") (pintype "passive"))
    )
    (net (code "41") (name "/DE06") (class "Default")
      (node (ref "J1") (pin "P$32") (pinfunction "X32_P$32") (pintype "bidirectional"))
      (node (ref "U8") (pin "25") (pinfunction "25_25") (pintype "passive"))
    )
    (net (code "42") (name "/DE07") (class "Default")
      (node (ref "J1") (pin "P$33") (pinfunction "X33_P$33") (pintype "bidirectional"))
      (node (ref "U8") (pin "24") (pinfunction "24_24") (pintype "passive"))
    )
    (net (code "43") (name "/DOT") (class "Default")
      (node (ref "U6") (pin "9") (pinfunction "QH_9") (pintype "output"))
      (node (ref "U8") (pin "2") (pinfunction "2_2") (pintype "passive"))
    )
    (net (code "44") (name "/DT00") (class "Default")
      (node (ref "C38") (pin "2") (pinfunction "2_2") (pintype "passive"))
      (node (ref "U5") (pin "9") (pinfunction "9_9") (pintype "passive"))
      (node (ref "U6") (pin "10") (pinfunction "SER_10") (pintype "input"))
      (node (ref "U6") (pin "11") (pinfunction "A_11") (pintype "input"))
    )
    (net (code "45") (name "/DT01") (class "Default")
      (node (ref "U5") (pin "10") (pinfunction "10_10") (pintype "passive"))
      (node (ref "U6") (pin "12") (pinfunction "B_12") (pintype "input"))
    )
    (net (code "46") (name "/DT02") (class "Default")
      (node (ref "U5") (pin "11") (pinfunction "11_11") (pintype "passive"))
      (node (ref "U6") (pin "13") (pinfunction "C_13") (pintype "input"))
    )
    (net (code "47") (name "/DT03") (class "Default")
      (node (ref "U5") (pin "13") (pinfunction "13_13") (pintype "passive"))
      (node (ref "U6") (pin "14") (pinfunction "D_14") (pintype "input"))
    )
    (net (code "48") (name "/DT04") (class "Default")
      (node (ref "U5") (pin "14") (pinfunction "14_14") (pintype "passive"))
      (node (ref "U6") (pin "3") (pinfunction "E_3") (pintype "input"))
    )
    (net (code "49") (name "/DT05") (class "Default")
      (node (ref "U5") (pin "15") (pinfunction "15_15") (pintype "passive"))
      (node (ref "U6") (pin "4") (pinfunction "F_4") (pintype "input"))
    )
    (net (code "50") (name "/DT06") (class "Default")
      (node (ref "U5") (pin "16") (pinfunction "16_16") (pintype "passive"))
      (node (ref "U6") (pin "5") (pinfunction "G_5") (pintype "input"))
    )
    (net (code "51") (name "/DT07") (class "Default")
      (node (ref "U5") (pin "17") (pinfunction "17_17") (pintype "passive"))
      (node (ref "U6") (pin "6") (pinfunction "H_6") (pintype "input"))
    )
    (net (code "52") (name "/G") (class "Default")
      (node (ref "U12") (pin "3") (pinfunction "3_3") (pintype "passive"))
      (node (ref "U8") (pin "21") (pinfunction "21_21") (pintype "passive"))
    )
    (net (code "53") (name "/INV") (class "Default")
      (node (ref "U12") (pin "1") (pinfunction "1_1") (pintype "passive"))
      (node (ref "U8") (pin "23") (pinfunction "23_23") (pintype "passive"))
    )
    (net (code "54") (name "/PALSW") (class "Default")
      (node (ref "JP3") (pin "1") (pinfunction "1_1") (pintype "passive"))
      (node (ref "U12") (pin "12") (pinfunction "12_12") (pintype "passive"))
    )
    (net (code "55") (name "/PR.AK") (class "Default")
      (node (ref "D13") (pin "C") (pinfunction "C_C") (pintype "passive"))
      (node (ref "D14") (pin "C") (pinfunction "C_C") (pintype "passive"))
      (node (ref "R30") (pin "2") (pinfunction "2_2") (pintype "passive"))
      (node (ref "R31") (pin "2") (pinfunction "2_2") (pintype "passive"))
      (node (ref "U7") (pin "41") (pinfunction "PR.AK_41") (pintype "bidirectional"))
    )
    (net (code "56") (name "/PRNT") (class "Default")
      (node (ref "U7") (pin "40") (pinfunction "PRNT_40") (pintype "bidirectional"))
      (node (ref "ZD2") (pin "A") (pinfunction "A_A") (pintype "passive"))
    )
    (net (code "57") (name "/R") (class "Default")
      (node (ref "U12") (pin "2") (pinfunction "2_2") (pintype "passive"))
      (node (ref "U8") (pin "20") (pinfunction "20_20") (pintype "passive"))
    )
    (net (code "58") (name "/RA0") (class "Default")
      (node (ref "U5") (pin "8") (pinfunction "8_8") (pintype "passive"))
      (node (ref "U7") (pin "8") (pinfunction "RA0_8") (pintype "bidirectional"))
    )
    (net (code "59") (name "/RA1") (class "Default")
      (node (ref "U5") (pin "7") (pinfunction "7_7") (pintype "passive"))
      (node (ref "U7") (pin "7") (pinfunction "RA1_7") (pintype "bidirectional"))
    )
    (net (code "60") (name "/RA2") (class "Default")
      (node (ref "U5") (pin "6") (pinfunction "6_6") (pintype "passive"))
      (node (ref "U7") (pin "6") (pinfunction "RA2_6") (pintype "bidirectional"))
    )
    (net (code "61") (name "/VA00") (class "Default")
      (node (ref "U3") (pin "8") (pinfunction "A0_8") (pintype "input"))
      (node (ref "U4") (pin "8") (pinfunction "A0_8") (pintype "input"))
      (node (ref "U7") (pin "3") (pinfunction "VA00_3") (pintype "bidirectional"))
    )
    (net (code "62") (name "/VA01") (class "Default")
      (node (ref "U3") (pin "7") (pinfunction "A1_7") (pintype "input"))
      (node (ref "U4") (pin "7") (pinfunction "A1_7") (pintype "input"))
      (node (ref "U7") (pin "4") (pinfunction "VA01_4") (pintype "bidirectional"))
    )
    (net (code "63") (name "/VA02") (class "Default")
      (node (ref "U3") (pin "6") (pinfunction "A2_6") (pintype "input"))
      (node (ref "U4") (pin "6") (pinfunction "A2_6") (pintype "input"))
      (node (ref "U7") (pin "5") (pinfunction "VA02_5") (pintype "bidirectional"))
    )
    (net (code "64") (name "/VA03") (class "Default")
      (node (ref "U3") (pin "5") (pinfunction "A3_5") (pintype "input"))
      (node (ref "U4") (pin "5") (pinfunction "A3_5") (pintype "input"))
      (node (ref "U7") (pin "53") (pinfunction "VA03_53") (pintype "bidirectional"))
    )
    (net (code "65") (name "/VA04") (class "Default")
      (node (ref "U3") (pin "4") (pinfunction "A4_4") (pintype "input"))
      (node (ref "U4") (pin "4") (pinfunction "A4_4") (pintype "input"))
      (node (ref "U7") (pin "54") (pinfunction "VA04_54") (pintype "bidirectional"))
    )
    (net (code "66") (name "/VA05") (class "Default")
      (node (ref "U3") (pin "3") (pinfunction "A5_3") (pintype "input"))
      (node (ref "U4") (pin "3") (pinfunction "A5_3") (pintype "input"))
      (node (ref "U7") (pin "55") (pinfunction "VA05_55") (pintype "bidirectional"))
    )
    (net (code "67") (name "/VA06") (class "Default")
      (node (ref "U3") (pin "2") (pinfunction "A6_2") (pintype "input"))
      (node (ref "U4") (pin "2") (pinfunction "A6_2") (pintype "input"))
      (node (ref "U7") (pin "56") (pinfunction "VA06_56") (pintype "bidirectional"))
    )
    (net (code "68") (name "/VA07") (class "Default")
      (node (ref "U3") (pin "1") (pinfunction "A7_1") (pintype "input"))
      (node (ref "U4") (pin "1") (pinfunction "A7_1") (pintype "input"))
      (node (ref "U7") (pin "57") (pinfunction "VA07_57") (pintype "bidirectional"))
    )
    (net (code "69") (name "/VA08") (class "Default")
      (node (ref "U3") (pin "23") (pinfunction "A8_23") (pintype "input"))
      (node (ref "U4") (pin "23") (pinfunction "A8_23") (pintype "input"))
      (node (ref "U7") (pin "58") (pinfunction "VA08_58") (pintype "bidirectional"))
    )
    (net (code "70") (name "/VA09") (class "Default")
      (node (ref "U3") (pin "22") (pinfunction "A9_22") (pintype "input"))
      (node (ref "U4") (pin "22") (pinfunction "A9_22") (pintype "input"))
      (node (ref "U7") (pin "59") (pinfunction "VA09_59") (pintype "bidirectional"))
    )
    (net (code "71") (name "/VA10") (class "Default")
      (node (ref "U3") (pin "19") (pinfunction "A10_19") (pintype "input"))
      (node (ref "U4") (pin "19") (pinfunction "A10_19") (pintype "input"))
      (node (ref "U7") (pin "60") (pinfunction "VA10_60") (pintype "bidirectional"))
    )
    (net (code "72") (name "/VD00") (class "Default")
      (node (ref "R6") (pin "1") (pinfunction "1_1") (pintype "passive"))
      (node (ref "U3") (pin "9") (pinfunction "I/O1_9") (pintype "bidirectional"))
      (node (ref "U5") (pin "5") (pinfunction "5_5") (pintype "passive"))
    )
    (net (code "73") (name "/VD01") (class "Default")
      (node (ref "R7") (pin "1") (pinfunction "1_1") (pintype "passive"))
      (node (ref "U3") (pin "10") (pinfunction "I/O2_10") (pintype "bidirectional"))
      (node (ref "U5") (pin "4") (pinfunction "4_4") (pintype "passive"))
    )
    (net (code "74") (name "/VD02") (class "Default")
      (node (ref "R8") (pin "1") (pinfunction "1_1") (pintype "passive"))
      (node (ref "U3") (pin "11") (pinfunction "I/O3_11") (pintype "bidirectional"))
      (node (ref "U5") (pin "3") (pinfunction "3_3") (pintype "passive"))
    )
    (net (code "75") (name "/VD03") (class "Default")
      (node (ref "R9") (pin "1") (pinfunction "1_1") (pintype "passive"))
      (node (ref "U3") (pin "13") (pinfunction "I/O4_13") (pintype "bidirectional"))
      (node (ref "U5") (pin "2") (pinfunction "2_2") (pintype "passive"))
    )
    (net (code "76") (name "/VD04") (class "Default")
      (node (ref "R10") (pin "1") (pinfunction "1_1") (pintype "passive"))
      (node (ref "U3") (pin "14") (pinfunction "I/O5_14") (pintype "bidirectional"))
      (node (ref "U5") (pin "1") (pinfunction "1_1") (pintype "passive"))
    )
    (net (code "77") (name "/VD05") (class "Default")
      (node (ref "R11") (pin "1") (pinfunction "1_1") (pintype "passive"))
      (node (ref "U3") (pin "15") (pinfunction "I/O6_15") (pintype "bidirectional"))
      (node (ref "U5") (pin "23") (pinfunction "23_23") (pintype "passive"))
    )
    (net (code "78") (name "/VD06") (class "Default")
      (node (ref "R12") (pin "1") (pinfunction "1_1") (pintype "passive"))
      (node (ref "U3") (pin "16") (pinfunction "I/O7_16") (pintype "bidirectional"))
      (node (ref "U5") (pin "22") (pinfunction "22_22") (pintype "passive"))
    )
    (net (code "79") (name "/VD07") (class "Default")
      (node (ref "R13") (pin "1") (pinfunction "1_1") (pintype "passive"))
      (node (ref "U3") (pin "17") (pinfunction "I/O8_17") (pintype "bidirectional"))
      (node (ref "U5") (pin "19") (pinfunction "19_19") (pintype "passive"))
    )
    (net (code "80") (name "/XA14") (class "Default")
      (node (ref "U15") (pin "6") (pinfunction "O_6") (pintype "output"))
      (node (ref "U7") (pin "15") (pinfunction "A14_15") (pintype "bidirectional"))
    )
    (net (code "81") (name "/XA15") (class "Default")
      (node (ref "U15") (pin "8") (pinfunction "O_8") (pintype "output"))
      (node (ref "U7") (pin "14") (pinfunction "A15_14") (pintype "bidirectional"))
    )
    (net (code "89") (name "/~{4{slash}Φ}") (class "Default")
      (node (ref "C2") (pin "1") (pinfunction "1_1") (pintype "passive"))
      (node (ref "U5") (pin "20") (pinfunction "20_20") (pintype "passive"))
      (node (ref "U7") (pin "63") (pinfunction "Φ/4_63") (pintype "bidirectional"))
      (node (ref "U8") (pin "3") (pinfunction "3_3") (pintype "passive"))
    )
    (net (code "90") (name "/~{BUSAK}") (class "Default")
      (node (ref "J1") (pin "P$42") (pinfunction "X42_P$42") (pintype "bidirectional"))
      (node (ref "R4") (pin "2") (pinfunction "2_2") (pintype "passive"))
      (node (ref "U1") (pin "23") (pinfunction "BUSAK_23") (pintype "output"))
    )
    (net (code "91") (name "/~{BUSREQ}") (class "Default")
      (node (ref "J1") (pin "P$4") (pinfunction "X4_P$4") (pintype "bidirectional"))
      (node (ref "R2") (pin "1") (pinfunction "1_1") (pintype "passive"))
      (node (ref "U1") (pin "25") (pinfunction "BUSRQ_25") (pintype "input"))
    )
    (net (code "92") (name "/~{CBLK}") (class "Default")
      (node (ref "U12") (pin "18") (pinfunction "18_18") (pintype "passive"))
      (node (ref "U7") (pin "46") (pinfunction "CBLK_46") (pintype "bidirectional"))
    )
    (net (code "93") (name "/~{CE}") (class "Default")
      (node (ref "J1") (pin "P$11") (pinfunction "X11_P$11") (pintype "bidirectional"))
      (node (ref "U11") (pin "8") (pinfunction "O_8") (pintype "output"))
    )
    (net (code "94") (name "/~{CSYNC}") (class "Default")
      (node (ref "J1") (pin "P$1") (pinfunction "X1_P$1") (pintype "bidirectional"))
      (node (ref "U12") (pin "5") (pinfunction "5_5") (pintype "passive"))
      (node (ref "U14") (pin "4") (pinfunction "A_4") (pintype "input"))
      (node (ref "U7") (pin "45") (pinfunction "CSYNC_45") (pintype "bidirectional"))
    )
    (net (code "95") (name "/~{DBE}") (class "Default")
      (node (ref "U7") (pin "49") (pinfunction "DBE_49") (pintype "bidirectional"))
      (node (ref "U8") (pin "6") (pinfunction "6_6") (pintype "passive"))
    )
    (net (code "96") (name "/~{EXBE}") (class "Default")
      (node (ref "U7") (pin "50") (pinfunction "EXBE_50") (pintype "bidirectional"))
      (node (ref "U8") (pin "5") (pinfunction "5_5") (pintype "passive"))
    )
    (net (code "97") (name "/~{HALT}") (class "Default")
      (node (ref "J1") (pin "P$41") (pinfunction "X41_P$41") (pintype "bidirectional"))
      (node (ref "U1") (pin "18") (pinfunction "HALT_18") (pintype "output"))
    )
    (net (code "98") (name "/~{INT}") (class "Default")
      (node (ref "J1") (pin "P$3") (pinfunction "X3_P$3") (pintype "bidirectional"))
      (node (ref "R3") (pin "1") (pinfunction "1_1") (pintype "passive"))
      (node (ref "U1") (pin "16") (pinfunction "INT_16") (pintype "input"))
    )
    (net (code "99") (name "/~{IORQ}") (class "Default")
      (node (ref "J1") (pin "P$43") (pinfunction "X43_P$43") (pintype "bidirectional"))
      (node (ref "U1") (pin "20") (pinfunction "IORQ_20") (pintype "output"))
      (node (ref "U7") (pin "39") (pinfunction "IORQ_39") (pintype "bidirectional"))
      (node (ref "U8") (pin "17") (pinfunction "17_17") (pintype "passive"))
    )
    (net (code "100") (name "/~{KEY}") (class "Default")
      (node (ref "U7") (pin "11") (pinfunction "KEY_11") (pintype "bidirectional"))
      (node (ref "U9") (pin "1") (pinfunction "1G_1") (pintype "input"))
      (node (ref "U9") (pin "15") (pinfunction "2G_15") (pintype "input"))
    )
    (net (code "101") (name "/~{LAEB}") (class "Default")
      (node (ref "U7") (pin "51") (pinfunction "LAEB_51") (pintype "bidirectional"))
      (node (ref "U8") (pin "4") (pinfunction "4_4") (pintype "passive"))
    )
    (net (code "102") (name "/~{M1}") (class "Default")
      (node (ref "J1") (pin "P$6") (pinfunction "X6_P$6") (pintype "bidirectional"))
      (node (ref "U1") (pin "27") (pinfunction "M1_27") (pintype "output"))
    )
    (net (code "103") (name "/~{MREQ}") (class "Default")
      (node (ref "J1") (pin "P$38") (pinfunction "X38_P$38") (pintype "bidirectional"))
      (node (ref "U1") (pin "19") (pinfunction "MREQ_19") (pintype "output"))
      (node (ref "U11") (pin "5") (pinfunction "I2_5") (pintype "input"))
      (node (ref "U7") (pin "37") (pinfunction "MREQ_37") (pintype "bidirectional"))
    )
    (net (code "104") (name "/~{MRST}") (class "Default")
      (node (ref "C1") (pin "+") (pinfunction "+_+") (pintype "passive"))
      (node (ref "D1") (pin "A") (pinfunction "A_A") (pintype "passive"))
      (node (ref "D15") (pin "A") (pinfunction "A_A") (pintype "passive"))
      (node (ref "J1") (pin "P$5") (pinfunction "X5_P$5") (pintype "bidirectional"))
      (node (ref "J2") (pin "15") (pinfunction "15_15") (pintype "passive"))
      (node (ref "R5") (pin "1") (pinfunction "1_1") (pintype "passive"))
      (node (ref "U7") (pin "30") (pinfunction "MRST_30") (pintype "bidirectional"))
      (node (ref "U8") (pin "19") (pinfunction "19_19") (pintype "passive"))
    )
    (net (code "105") (name "/~{NMI}") (class "Default")
      (node (ref "J1") (pin "P$39") (pinfunction "X39_P$39") (pintype "bidirectional"))
      (node (ref "R1") (pin "1") (pinfunction "1_1") (pintype "passive"))
      (node (ref "U1") (pin "17") (pinfunction "NMI_17") (pintype "input"))
    )
    (net (code "106") (name "/~{RD}") (class "Default")
      (node (ref "J1") (pin "P$35") (pinfunction "X35_P$35") (pintype "bidirectional"))
      (node (ref "U1") (pin "21") (pinfunction "RD_21") (pintype "output"))
      (node (ref "U7") (pin "38") (pinfunction "RD_38") (pintype "bidirectional"))
    )
    (net (code "107") (name "/~{RFSH}") (class "Default")
      (node (ref "J1") (pin "P$7") (pinfunction "X7_P$7") (pintype "bidirectional"))
      (node (ref "U1") (pin "28") (pinfunction "RFSH_28") (pintype "output"))
    )
    (net (code "108") (name "/~{RM1}") (class "Default")
      (node (ref "U3") (pin "18") (pinfunction "~{CS}_18") (pintype "input"))
      (node (ref "U7") (pin "62") (pinfunction "RM1_62") (pintype "bidirectional"))
    )
    (net (code "109") (name "/~{RM2}") (class "Default")
      (node (ref "U4") (pin "18") (pinfunction "~{CS}_18") (pintype "input"))
      (node (ref "U7") (pin "61") (pinfunction "RM2_61") (pintype "bidirectional"))
    )
    (net (code "110") (name "/~{ROM}") (class "Default")
      (node (ref "U2") (pin "20") (pinfunction "20_20") (pintype "passive"))
      (node (ref "U7") (pin "10") (pinfunction "ROM_10") (pintype "bidirectional"))
    )
    (net (code "111") (name "/~{RST}") (class "Default")
      (node (ref "D15") (pin "C") (pinfunction "C_C") (pintype "passive"))
      (node (ref "R45") (pin "2") (pinfunction "2_2") (pintype "passive"))
      (node (ref "U1") (pin "26") (pinfunction "RESET_26") (pintype "input"))
    )
    (net (code "112") (name "/~{R{slash}W}") (class "Default")
      (node (ref "U3") (pin "21") (pinfunction "~{WE}_21") (pintype "input"))
      (node (ref "U4") (pin "21") (pinfunction "~{WE}_21") (pintype "input"))
      (node (ref "U7") (pin "52") (pinfunction "R/~{W}_52") (pintype "bidirectional"))
    )
    (net (code "113") (name "/~{WAIT}") (class "Default")
      (node (ref "J1") (pin "P$40") (pinfunction "X40_P$40") (pintype "bidirectional"))
      (node (ref "R25") (pin "1") (pinfunction "1_1") (pintype "passive"))
      (node (ref "U1") (pin "24") (pinfunction "WAIT_24") (pintype "input"))
      (node (ref "U7") (pin "35") (pinfunction "WAIT_35") (pintype "bidirectional"))
    )
    (net (code "114") (name "/~{WR}") (class "Default")
      (node (ref "J1") (pin "P$37") (pinfunction "X37_P$37") (pintype "bidirectional"))
      (node (ref "U1") (pin "22") (pinfunction "WR_22") (pintype "output"))
      (node (ref "U7") (pin "36") (pinfunction "WR_36") (pintype "bidirectional"))
      (node (ref "U8") (pin "18") (pinfunction "18_18") (pintype "passive"))
    )
    (net (code "115") (name "2Φ") (class "Default")
      (node (ref "JP6") (pin "1") (pinfunction "1_1") (pintype "passive"))
      (node (ref "R52") (pin "1") (pinfunction "1_1") (pintype "passive"))
      (node (ref "U6") (pin "2") (pinfunction "CLK_2") (pintype "input"))
      (node (ref "U7") (pin "2") (pinfunction "2Φ_2") (pintype "bidirectional"))
    )
    (net (code "116") (name "A14") (class "Default")
      (node (ref "D8") (pin "C") (pinfunction "C_C") (pintype "passive"))
      (node (ref "J1") (pin "P$10") (pinfunction "X10_P$10") (pintype "bidirectional"))
      (node (ref "U1") (pin "4") (pinfunction "A14_4") (pintype "output"))
      (node (ref "U11") (pin "10") (pinfunction "I1_10") (pintype "input"))
      (node (ref "U15") (pin "4") (pinfunction "I0_4") (pintype "input"))
    )
    (net (code "117") (name "A15") (class "Default")
      (node (ref "D9") (pin "C") (pinfunction "C_C") (pintype "passive"))
      (node (ref "J1") (pin "P$9") (pinfunction "X9_P$9") (pintype "bidirectional"))
      (node (ref "U1") (pin "5") (pinfunction "A15_5") (pintype "output"))
      (node (ref "U11") (pin "11") (pinfunction "I2_11") (pintype "input"))
      (node (ref "U15") (pin "10") (pinfunction "I1_10") (pintype "input"))
    )
    (net (code "118") (name "CASS.IN") (class "Default")
      (node (ref "Q1") (pin "1") (pinfunction "C_1") (pintype "passive"))
      (node (ref "R18") (pin "2") (pinfunction "2_2") (pintype "passive"))
      (node (ref "U7") (pin "42") (pinfunction "CASS.IN_42") (pintype "bidirectional"))
    )
    (net (code "119") (name "CASS.OUT") (class "Default")
      (node (ref "C30") (pin "-") (pinfunction "-_-") (pintype "passive"))
      (node (ref "R24") (pin "1") (pinfunction "1_1") (pintype "passive"))
      (node (ref "U7") (pin "43") (pinfunction "CASS.OUT_43") (pintype "bidirectional"))
    )
    (net (code "120") (name "COMP-LO") (class "Default")
      (node (ref "MOD1") (pin "1") (pinfunction "1_1") (pintype "passive"))
      (node (ref "R41") (pin "1") (pinfunction "1_1") (pintype "passive"))
      (node (ref "R42") (pin "1") (pinfunction "1_1") (pintype "passive"))
    )
    (net (code "121") (name "D00") (class "Default")
      (node (ref "U1") (pin "14") (pinfunction "D0_14") (pintype "bidirectional"))
      (node (ref "U2") (pin "9") (pinfunction "9_9") (pintype "passive"))
      (node (ref "U7") (pin "9") (pinfunction "D0_9") (pintype "bidirectional"))
      (node (ref "U8") (pin "9") (pinfunction "9_9") (pintype "passive"))
      (node (ref "U9") (pin "11") (pinfunction "2Y1_11") (pintype "tri_state"))
    )
    (net (code "122") (name "D01") (class "Default")
      (node (ref "U1") (pin "15") (pinfunction "D1_15") (pintype "bidirectional"))
      (node (ref "U2") (pin "10") (pinfunction "10_10") (pintype "passive"))
      (node (ref "U8") (pin "10") (pinfunction "10_10") (pintype "passive"))
      (node (ref "U9") (pin "5") (pinfunction "1Y2_5") (pintype "tri_state"))
    )
    (net (code "123") (name "D02") (class "Default")
      (node (ref "U1") (pin "12") (pinfunction "D2_12") (pintype "bidirectional"))
      (node (ref "U2") (pin "11") (pinfunction "11_11") (pintype "passive"))
      (node (ref "U8") (pin "11") (pinfunction "11_11") (pintype "passive"))
      (node (ref "U9") (pin "9") (pinfunction "1Y4_9") (pintype "tri_state"))
    )
    (net (code "124") (name "D03") (class "Default")
      (node (ref "U1") (pin "8") (pinfunction "D3_8") (pintype "bidirectional"))
      (node (ref "U2") (pin "13") (pinfunction "13_13") (pintype "passive"))
      (node (ref "U8") (pin "12") (pinfunction "12_12") (pintype "passive"))
      (node (ref "U9") (pin "13") (pinfunction "2Y2_13") (pintype "tri_state"))
    )
    (net (code "125") (name "D04") (class "Default")
      (node (ref "U1") (pin "7") (pinfunction "D4_7") (pintype "bidirectional"))
      (node (ref "U2") (pin "14") (pinfunction "14_14") (pintype "passive"))
      (node (ref "U8") (pin "13") (pinfunction "13_13") (pintype "passive"))
      (node (ref "U9") (pin "3") (pinfunction "1Y1_3") (pintype "tri_state"))
    )
    (net (code "126") (name "D05") (class "Default")
      (node (ref "U1") (pin "9") (pinfunction "D5_9") (pintype "bidirectional"))
      (node (ref "U2") (pin "15") (pinfunction "15_15") (pintype "passive"))
      (node (ref "U8") (pin "14") (pinfunction "14_14") (pintype "passive"))
      (node (ref "U9") (pin "7") (pinfunction "1Y3_7") (pintype "tri_state"))
    )
    (net (code "127") (name "GND") (class "Default")
      (node (ref "C1") (pin "-") (pinfunction "-_-") (pintype "passive"))
      (node (ref "C10") (pin "1") (pinfunction "1_1") (pintype "passive"))
      (node (ref "C11") (pin "2") (pinfunction "2_2") (pintype "passive"))
      (node (ref "C12") (pin "-") (pinfunction "-_-") (pintype "passive"))
      (node (ref "C13") (pin "+") (pinfunction "+_+") (pintype "passive"))
      (node (ref "C15") (pin "2") (pinfunction "2_2") (pintype "passive"))
      (node (ref "C16") (pin "1") (pinfunction "1_1") (pintype "passive"))
      (node (ref "C17") (pin "2") (pinfunction "2_2") (pintype "passive"))
      (node (ref "C18") (pin "1") (pinfunction "1_1") (pintype "passive"))
      (node (ref "C19") (pin "1") (pinfunction "1_1") (pintype "passive"))
      (node (ref "C20") (pin "2") (pinfunction "2_2") (pintype "passive"))
      (node (ref "C21") (pin "2") (pinfunction "2_2") (pintype "passive"))
      (node (ref "C22") (pin "2") (pinfunction "2_2") (pintype "passive"))
      (node (ref "C24") (pin "2") (pinfunction "2_2") (pintype "passive"))
      (node (ref "C25") (pin "2") (pinfunction "2_2") (pintype "passive"))
      (node (ref "C26") (pin "2") (pinfunction "2_2") (pintype "passive"))
      (node (ref "C27") (pin "2") (pinfunction "2_2") (pintype "passive"))
      (node (ref "C28") (pin "1") (pinfunction "1_1") (pintype "passive"))
      (node (ref "C29") (pin "1") (pinfunction "1_1") (pintype "passive"))
      (node (ref "C3") (pin "2") (pinfunction "2_2") (pintype "passive"))
      (node (ref "C31") (pin "1") (pinfunction "1_1") (pintype "passive"))
      (node (ref "C33") (pin "1") (pinfunction "1_1") (pintype "passive"))
      (node (ref "C35") (pin "2") (pinfunction "2_2") (pintype "passive"))
      (node (ref "C36") (pin "1") (pinfunction "1_1") (pintype "passive"))
      (node (ref "C38") (pin "1") (pinfunction "1_1") (pintype "passive"))
      (node (ref "C40") (pin "2") (pinfunction "2_2") (pintype "passive"))
      (node (ref "C41") (pin "2") (pinfunction "2_2") (pintype "passive"))
      (node (ref "C42") (pin "2") (pinfunction "2_2") (pintype "passive"))
      (node (ref "C43") (pin "2") (pinfunction "2_2") (pintype "passive"))
      (node (ref "C44") (pin "2") (pinfunction "2_2") (pintype "passive"))
      (node (ref "C6") (pin "-") (pinfunction "-_-") (pintype "passive"))
      (node (ref "C7") (pin "1") (pinfunction "1_1") (pintype "passive"))
      (node (ref "C8") (pin "-") (pinfunction "-_-") (pintype "passive"))
      (node (ref "C9") (pin "-") (pinfunction "-_-") (pintype "passive"))
      (node (ref "D10") (pin "A") (pinfunction "A_A") (pintype "passive"))
      (node (ref "D11") (pin "A") (pinfunction "A_A") (pintype "passive"))
      (node (ref "D12") (pin "A") (pinfunction "A_A") (pintype "passive"))
      (node (ref "D13") (pin "A") (pinfunction "A_A") (pintype "passive"))
      (node (ref "D16") (pin "A") (pinfunction "A_A") (pintype "passive"))
      (node (ref "F1") (pin "0") (pinfunction "GND_0") (pintype "power_in"))
      (node (ref "F2") (pin "2") (pinfunction "2_2") (pintype "passive"))
      (node (ref "F3") (pin "0") (pinfunction "GND_0") (pintype "power_in"))
      (node (ref "J1") (pin "P$34") (pinfunction "X34_P$34") (pintype "bidirectional"))
      (node (ref "J1") (pin "P$44") (pinfunction "X44_P$44") (pintype "bidirectional"))
      (node (ref "J2") (pin "16") (pinfunction "16_16") (pintype "passive"))
      (node (ref "J2") (pin "17") (pinfunction "17_17") (pintype "passive"))
      (node (ref "J4") (pin "SLEEVE") (pinfunction "SLEEVE_SLEEVE") (pintype "bidirectional"))
      (node (ref "J5") (pin "2") (pinfunction "2_2") (pintype "bidirectional"))
      (node (ref "JP4") (pin "4") (pinfunction "4_4") (pintype "passive"))
      (node (ref "LED1") (pin "K") (pinfunction "C_K") (pintype "passive"))
      (node (ref "Q1") (pin "3") (pinfunction "E_3") (pintype "passive"))
      (node (ref "Q5") (pin "3") (pinfunction "E_3") (pintype "passive"))
      (node (ref "Q8") (pin "3") (pinfunction "E_3") (pintype "passive"))
      (node (ref "R15") (pin "2") (pinfunction "2_2") (pintype "passive"))
      (node (ref "R20") (pin "1") (pinfunction "1_1") (pintype "passive"))
      (node (ref "R22") (pin "1") (pinfunction "1_1") (pintype "passive"))
      (node (ref "R23") (pin "1") (pinfunction "1_1") (pintype "passive"))
      (node (ref "R30") (pin "1") (pinfunction "1_1") (pintype "passive"))
      (node (ref "R33") (pin "2") (pinfunction "2_2") (pintype "passive"))
      (node (ref "R38") (pin "2") (pinfunction "2_2") (pintype "passive"))
      (node (ref "R39") (pin "2") (pinfunction "2_2") (pintype "passive"))
      (node (ref "R41") (pin "2") (pinfunction "2_2") (pintype "passive"))
      (node (ref "R44") (pin "2") (pinfunction "2_2") (pintype "passive"))
      (node (ref "R45") (pin "1") (pinfunction "1_1") (pintype "passive"))
      (node (ref "R53") (pin "1") (pinfunction "1_1") (pintype "passive"))
      (node (ref "R55") (pin "1") (pinfunction "1_1") (pintype "passive"))
      (node (ref "SW2") (pin "3") (pinfunction "O_3") (pintype "passive"))
      (node (ref "U1") (pin "29") (pinfunction "GND_29") (pintype "power_in"))
      (node (ref "U10") (pin "2") (pinfunction "GND_2") (pintype "passive"))
      (node (ref "U12") (pin "16") (pinfunction "16_16") (pintype "passive"))
      (node (ref "U14") (pin "1") (pinfunction "T1_1") (pintype "input"))
      (node (ref "U2") (pin "12") (pinfunction "12_12") (pintype "passive"))
      (node (ref "U3") (pin "20") (pinfunction "~{OE}_20") (pintype "input"))
      (node (ref "U4") (pin "20") (pinfunction "~{OE}_20") (pintype "input"))
      (node (ref "U5") (pin "12") (pinfunction "12_12") (pintype "passive"))
      (node (ref "U5") (pin "18") (pinfunction "18_18") (pintype "passive"))
      (node (ref "U6") (pin "15") (pinfunction "INH_15") (pintype "input"))
      (node (ref "U7") (pin "1") (pinfunction "GND_1") (pintype "power_in"))
      (node (ref "U7") (pin "33") (pinfunction "P33_33") (pintype "bidirectional"))
      (node (ref "U8") (pin "1") (pinfunction "1_1") (pintype "passive"))
      (node (ref "ZD1") (pin "A") (pinfunction "A_A") (pintype "passive"))
    )
    (net (code "128") (name "Net-(C4-Pad1)") (class "Default")
      (node (ref "C4") (pin "1") (pinfunction "1_1") (pintype "passive"))
      (node (ref "J5") (pin "3") (pinfunction "3_3") (pintype "bidirectional"))
      (node (ref "R39") (pin "1") (pinfunction "1_1") (pintype "passive"))
    )
    (net (code "129") (name "Net-(C5-Pad-)") (class "Default")
      (node (ref "C5") (pin "-") (pinfunction "-_-") (pintype "passive"))
      (node (ref "R16") (pin "1") (pinfunction "1_1") (pintype "passive"))
    )
    (net (code "130") (name "Net-(C8-Pad+)") (class "Default")
      (node (ref "C8") (pin "+") (pinfunction "+_+") (pintype "passive"))
      (node (ref "F3") (pin "2") (pinfunction "2_2") (pintype "passive"))
      (node (ref "SW1") (pin "P$2A") (pinfunction "P$2A_P$2A") (pintype "bidirectional"))
      (node (ref "SW1") (pin "P$2B") (pinfunction "P$2B_P$2B") (pintype "bidirectional"))
    )
    (net (code "131") (name "Net-(C11-Pad1)") (class "Default")
      (node (ref "C11") (pin "1") (pinfunction "1_1") (pintype "passive"))
      (node (ref "L5") (pin "2") (pinfunction "2_2") (pintype "passive"))
      (node (ref "R48") (pin "2") (pinfunction "2_2") (pintype "passive"))
    )
    (net (code "132") (name "Net-(C13-Pad-)") (class "Default")
      (node (ref "C13") (pin "-") (pinfunction "-_-") (pintype "passive"))
      (node (ref "R48") (pin "1") (pinfunction "1_1") (pintype "passive"))
      (node (ref "SW1") (pin "P$3A") (pinfunction "P$3A_P$3A") (pintype "bidirectional"))
      (node (ref "SW1") (pin "P$3B") (pinfunction "P$3B_P$3B") (pintype "bidirectional"))
    )
    (net (code "133") (name "Net-(C14-Pad1)") (class "Default")
      (node (ref "C14") (pin "1") (pinfunction "1_1") (pintype "passive"))
      (node (ref "U12") (pin "11") (pinfunction "11_11") (pintype "passive"))
    )
    (net (code "134") (name "Net-(C14-Pad2)") (class "Default")
      (node (ref "C14") (pin "2") (pinfunction "2_2") (pintype "passive"))
      (node (ref "C32") (pin "2") (pinfunction "2_2") (pintype "passive"))
      (node (ref "L-V1") (pin "P$1") (pinfunction "P$1_P$1") (pintype "bidirectional"))
      (node (ref "L-V1") (pin "P$3") (pinfunction "P$1_P$3") (pintype "bidirectional"))
    )
    (net (code "135") (name "Net-(C16-Pad2)") (class "Default")
      (node (ref "C16") (pin "2") (pinfunction "2_2") (pintype "passive"))
      (node (ref "L3") (pin "1") (pinfunction "1_1") (pintype "passive"))
      (node (ref "L4") (pin "1") (pinfunction "1_1") (pintype "passive"))
    )
    (net (code "136") (name "Net-(C18-Pad2)") (class "Default")
      (node (ref "C18") (pin "2") (pinfunction "2_2") (pintype "passive"))
      (node (ref "L2") (pin "1") (pinfunction "1_1") (pintype "passive"))
      (node (ref "L3") (pin "2") (pinfunction "2_2") (pintype "passive"))
    )
    (net (code "137") (name "Net-(C19-Pad2)") (class "Default")
      (node (ref "C19") (pin "2") (pinfunction "2_2") (pintype "passive"))
      (node (ref "L1") (pin "1") (pinfunction "1_1") (pintype "passive"))
      (node (ref "L2") (pin "2") (pinfunction "2_2") (pintype "passive"))
    )
    (net (code "138") (name "Net-(C23-Pad2)") (class "Default")
      (node (ref "C23") (pin "2") (pinfunction "2_2") (pintype "passive"))
      (node (ref "C44") (pin "1") (pinfunction "1_1") (pintype "passive"))
      (node (ref "XTAL2") (pin "2") (pinfunction "2_2") (pintype "passive"))
    )
    (net (code "139") (name "Net-(C29-Pad2)") (class "Default")
      (node (ref "C29") (pin "2") (pinfunction "2_2") (pintype "passive"))
      (node (ref "R33") (pin "1") (pinfunction "1_1") (pintype "passive"))
      (node (ref "U12") (pin "17") (pinfunction "17_17") (pintype "passive"))
    )
    (net (code "140") (name "Net-(C30-Pad+)") (class "Default")
      (node (ref "C30") (pin "+") (pinfunction "+_+") (pintype "passive"))
      (node (ref "R43") (pin "1") (pinfunction "1_1") (pintype "passive"))
    )
    (net (code "141") (name "Net-(C31-Pad2)") (class "Default")
      (node (ref "C31") (pin "2") (pinfunction "2_2") (pintype "passive"))
      (node (ref "R35") (pin "2") (pinfunction "2_2") (pintype "passive"))
      (node (ref "R53") (pin "2") (pinfunction "2_2") (pintype "passive"))
      (node (ref "R54") (pin "2") (pinfunction "2_2") (pintype "passive"))
    )
    (net (code "142") (name "Net-(CT1-A)") (class "Default")
      (node (ref "CT1") (pin "2") (pinfunction "A_2") (pintype "passive"))
      (node (ref "U12") (pin "14") (pinfunction "14_14") (pintype "passive"))
    )
    (net (code "143") (name "Net-(CT1-E)") (class "Default")
      (node (ref "C34") (pin "1") (pinfunction "1_1") (pintype "passive"))
      (node (ref "CT1") (pin "1") (pinfunction "E_1") (pintype "passive"))
      (node (ref "XTAL1") (pin "1") (pinfunction "1_1") (pintype "passive"))
    )
    (net (code "144") (name "Net-(D2-PadA)") (class "Default")
      (node (ref "D2") (pin "A") (pinfunction "A_A") (pintype "passive"))
      (node (ref "J2") (pin "1") (pinfunction "1_1") (pintype "passive"))
    )
    (net (code "145") (name "Net-(D3-PadA)") (class "Default")
      (node (ref "D3") (pin "A") (pinfunction "A_A") (pintype "passive"))
      (node (ref "J2") (pin "2") (pinfunction "2_2") (pintype "passive"))
    )
    (net (code "146") (name "Net-(D4-PadA)") (class "Default")
      (node (ref "D4") (pin "A") (pinfunction "A_A") (pintype "passive"))
      (node (ref "J2") (pin "3") (pinfunction "3_3") (pintype "passive"))
    )
    (net (code "147") (name "Net-(D5-PadA)") (class "Default")
      (node (ref "D5") (pin "A") (pinfunction "A_A") (pintype "passive"))
      (node (ref "J2") (pin "4") (pinfunction "4_4") (pintype "passive"))
    )
    (net (code "148") (name "Net-(D6-PadA)") (class "Default")
      (node (ref "D6") (pin "A") (pinfunction "A_A") (pintype "passive"))
      (node (ref "J2") (pin "5") (pinfunction "5_5") (pintype "passive"))
    )
    (net (code "149") (name "Net-(D7-PadA)") (class "Default")
      (node (ref "D7") (pin "A") (pinfunction "A_A") (pintype "passive"))
      (node (ref "J2") (pin "6") (pinfunction "6_6") (pintype "passive"))
    )
    (net (code "150") (name "Net-(D8-PadA)") (class "Default")
      (node (ref "D8") (pin "A") (pinfunction "A_A") (pintype "passive"))
      (node (ref "J2") (pin "7") (pinfunction "7_7") (pintype "passive"))
    )
    (net (code "151") (name "Net-(D9-PadA)") (class "Default")
      (node (ref "D9") (pin "A") (pinfunction "A_A") (pintype "passive"))
      (node (ref "J2") (pin "8") (pinfunction "8_8") (pintype "passive"))
    )
    (net (code "152") (name "Net-(F1-Pad1)") (class "Default")
      (node (ref "F1") (pin "1") (pinfunction "1_1") (pintype "passive"))
      (node (ref "L6") (pin "2") (pinfunction "2_2") (pintype "passive"))
    )
    (net (code "153") (name "Net-(F2-GND)") (class "Default")
      (node (ref "C9") (pin "+") (pinfunction "+_+") (pintype "passive"))
      (node (ref "F1") (pin "2") (pinfunction "2_2") (pintype "passive"))
      (node (ref "F2") (pin "0") (pinfunction "GND_0") (pintype "power_in"))
      (node (ref "SW1") (pin "P$1A") (pinfunction "P$1A_P$1A") (pintype "bidirectional"))
      (node (ref "SW1") (pin "P$1B") (pinfunction "P$1B_P$1B") (pintype "bidirectional"))
    )
    (net (code "154") (name "Net-(F2-Pad1)") (class "Default")
      (node (ref "F2") (pin "1") (pinfunction "1_1") (pintype "passive"))
      (node (ref "L7") (pin "2") (pinfunction "2_2") (pintype "passive"))
    )
    (net (code "155") (name "Net-(F3-Pad1)") (class "Default")
      (node (ref "F3") (pin "1") (pinfunction "1_1") (pintype "passive"))
      (node (ref "L8") (pin "2") (pinfunction "2_2") (pintype "passive"))
    )
    (net (code "156") (name "Net-(J4-PadRING)") (class "Default")
      (node (ref "J4") (pin "RING") (pinfunction "RING_RING") (pintype "bidirectional"))
      (node (ref "J4") (pin "RSH") (pinfunction "RSH_RSH") (pintype "bidirectional"))
      (node (ref "R31") (pin "1") (pinfunction "1_1") (pintype "passive"))
    )
    (net (code "157") (name "Net-(J4-PadTIP)") (class "Default")
      (node (ref "J4") (pin "TIP") (pinfunction "TIP_TIP") (pintype "bidirectional"))
      (node (ref "J4") (pin "TSH") (pinfunction "TSH_TSH") (pintype "bidirectional"))
      (node (ref "R29") (pin "1") (pinfunction "1_1") (pintype "passive"))
    )
    (net (code "158") (name "Net-(J5-Pad1)") (class "Default")
      (node (ref "J5") (pin "1") (pinfunction "1_1") (pintype "bidirectional"))
      (node (ref "R23") (pin "2") (pinfunction "2_2") (pintype "passive"))
      (node (ref "R24") (pin "2") (pinfunction "2_2") (pintype "passive"))
    )
    (net (code "159") (name "Net-(L1-Pad2)") (class "Default")
      (node (ref "L1") (pin "2") (pinfunction "2_2") (pintype "passive"))
      (node (ref "R38") (pin "1") (pinfunction "1_1") (pintype "passive"))
      (node (ref "U12") (pin "7") (pinfunction "7_7") (pintype "passive"))
    )
    (net (code "160") (name "Net-(L4-Pad2)") (class "Default")
      (node (ref "L4") (pin "2") (pinfunction "2_2") (pintype "passive"))
      (node (ref "R32") (pin "1") (pinfunction "1_1") (pintype "passive"))
    )
    (net (code "161") (name "Net-(LED1-PadA)") (class "Default")
      (node (ref "LED1") (pin "A") (pinfunction "A_A") (pintype "passive"))
      (node (ref "R46") (pin "1") (pinfunction "1_1") (pintype "passive"))
    )
    (net (code "162") (name "Net-(MOD2-Pad1)") (class "Default")
      (node (ref "MOD2") (pin "1") (pinfunction "1_1") (pintype "passive"))
      (node (ref "R40") (pin "1") (pinfunction "1_1") (pintype "passive"))
    )
    (net (code "163") (name "Net-(Q1-B)") (class "Default")
      (node (ref "D11") (pin "C") (pinfunction "C_C") (pintype "passive"))
      (node (ref "Q1") (pin "2") (pinfunction "B_2") (pintype "passive"))
      (node (ref "R16") (pin "2") (pinfunction "2_2") (pintype "passive"))
      (node (ref "R17") (pin "2") (pinfunction "2_2") (pintype "passive"))
    )
    (net (code "164") (name "Net-(Q2-B)") (class "Default")
      (node (ref "C4") (pin "2") (pinfunction "2_2") (pintype "passive"))
      (node (ref "D12") (pin "C") (pinfunction "C_C") (pintype "passive"))
      (node (ref "Q2") (pin "2") (pinfunction "B_2") (pintype "passive"))
      (node (ref "R21") (pin "2") (pinfunction "2_2") (pintype "passive"))
      (node (ref "R22") (pin "2") (pinfunction "2_2") (pintype "passive"))
    )
    (net (code "165") (name "Net-(Q2-C)") (class "Default")
      (node (ref "C5") (pin "+") (pinfunction "+_+") (pintype "passive"))
      (node (ref "Q2") (pin "1") (pinfunction "C_1") (pintype "passive"))
      (node (ref "R19") (pin "2") (pinfunction "2_2") (pintype "passive"))
    )
    (net (code "166") (name "Net-(Q2-E)") (class "Default")
      (node (ref "Q2") (pin "3") (pinfunction "E_3") (pintype "passive"))
      (node (ref "R20") (pin "2") (pinfunction "2_2") (pintype "passive"))
    )
    (net (code "167") (name "Net-(Q3-B)") (class "Default")
      (node (ref "Q3") (pin "2") (pinfunction "B_2") (pintype "passive"))
      (node (ref "R27") (pin "1") (pinfunction "1_1") (pintype "passive"))
      (node (ref "R36") (pin "2") (pinfunction "2_2") (pintype "passive"))
    )
    (net (code "168") (name "Net-(Q3-C)") (class "Default")
      (node (ref "Q3") (pin "1") (pinfunction "C_1") (pintype "passive"))
      (node (ref "R28") (pin "1") (pinfunction "1_1") (pintype "passive"))
      (node (ref "R29") (pin "2") (pinfunction "2_2") (pintype "passive"))
    )
    (net (code "169") (name "Net-(Q4-B)") (class "Default")
      (node (ref "C7") (pin "2") (pinfunction "2_2") (pintype "passive"))
      (node (ref "Q4") (pin "1") (pinfunction "B_1") (pintype "passive"))
      (node (ref "R37") (pin "1") (pinfunction "1_1") (pintype "passive"))
      (node (ref "ZD1") (pin "C") (pinfunction "C_C") (pintype "passive"))
    )
    (net (code "170") (name "Net-(Q4-C)") (class "Default")
      (node (ref "Q4") (pin "2") (pinfunction "C_2") (pintype "passive"))
      (node (ref "R37") (pin "2") (pinfunction "2_2") (pintype "passive"))
      (node (ref "SW1") (pin "P$2C") (pinfunction "P$2C_P$2C") (pintype "bidirectional"))
    )
    (net (code "171") (name "Net-(Q5-B)") (class "Default")
      (node (ref "C2") (pin "2") (pinfunction "2_2") (pintype "passive"))
      (node (ref "D10") (pin "C") (pinfunction "C_C") (pintype "passive"))
      (node (ref "Q5") (pin "2") (pinfunction "B_2") (pintype "passive"))
      (node (ref "R15") (pin "1") (pinfunction "1_1") (pintype "passive"))
    )
    (net (code "172") (name "Net-(Q5-C)") (class "Default")
      (node (ref "Q5") (pin "1") (pinfunction "C_1") (pintype "passive"))
      (node (ref "R14") (pin "2") (pinfunction "2_2") (pintype "passive"))
      (node (ref "U6") (pin "1") (pinfunction "SH/~{LD}_1") (pintype "input"))
    )
    (net (code "173") (name "Net-(Q6-B)") (class "Default")
      (node (ref "Q6") (pin "2") (pinfunction "B_2") (pintype "passive"))
      (node (ref "R34") (pin "2") (pinfunction "2_2") (pintype "passive"))
      (node (ref "R35") (pin "1") (pinfunction "1_1") (pintype "passive"))
    )
    (net (code "174") (name "Net-(Q6-C)") (class "Default")
      (node (ref "C39") (pin "1") (pinfunction "1_1") (pintype "passive"))
      (node (ref "Q6") (pin "1") (pinfunction "C_1") (pintype "passive"))
      (node (ref "R60") (pin "1") (pinfunction "1_1") (pintype "passive"))
    )
    (net (code "175") (name "Net-(Q6-E)") (class "Default")
      (node (ref "Q6") (pin "3") (pinfunction "E_3") (pintype "passive"))
      (node (ref "R44") (pin "1") (pinfunction "1_1") (pintype "passive"))
      (node (ref "R59") (pin "2") (pinfunction "2_2") (pintype "passive"))
      (node (ref "U16") (pin "2") (pinfunction "B_2") (pintype "passive"))
    )
    (net (code "176") (name "Net-(Q7-B)") (class "Default")
      (node (ref "Q7") (pin "2") (pinfunction "B_2") (pintype "passive"))
      (node (ref "U16") (pin "1") (pinfunction "A_1") (pintype "passive"))
      (node (ref "U16") (pin "11") (pinfunction "A_11") (pintype "passive"))
    )
    (net (code "177") (name "Net-(Q7-E)") (class "Default")
      (node (ref "Q7") (pin "3") (pinfunction "E_3") (pintype "passive"))
      (node (ref "R42") (pin "2") (pinfunction "2_2") (pintype "passive"))
    )
    (net (code "178") (name "Net-(Q8-B)") (class "Default")
      (node (ref "C34") (pin "2") (pinfunction "2_2") (pintype "passive"))
      (node (ref "Q8") (pin "2") (pinfunction "B_2") (pintype "passive"))
      (node (ref "R56") (pin "1") (pinfunction "1_1") (pintype "passive"))
    )
    (net (code "179") (name "Net-(Q8-C)") (class "Default")
      (node (ref "C37") (pin "2") (pinfunction "2_2") (pintype "passive"))
      (node (ref "Q8") (pin "1") (pinfunction "C_1") (pintype "passive"))
      (node (ref "R56") (pin "2") (pinfunction "2_2") (pintype "passive"))
      (node (ref "R57") (pin "1") (pinfunction "1_1") (pintype "passive"))
    )
    (net (code "180") (name "Net-(R26-Pad2)") (class "Default")
      (node (ref "R26") (pin "2") (pinfunction "2_2") (pintype "passive"))
      (node (ref "U12") (pin "9") (pinfunction "9_9") (pintype "passive"))
    )
    (net (code "181") (name "Net-(R32-Pad2)") (class "Default")
      (node (ref "R32") (pin "2") (pinfunction "2_2") (pintype "passive"))
      (node (ref "U12") (pin "6") (pinfunction "6_6") (pintype "passive"))
    )
    (net (code "182") (name "Net-(R34-Pad1)") (class "Default")
      (node (ref "R34") (pin "1") (pinfunction "1_1") (pintype "passive"))
      (node (ref "U12") (pin "8") (pinfunction "8_8") (pintype "passive"))
    )
    (net (code "183") (name "Net-(R36-Pad1)") (class "Default")
      (node (ref "R36") (pin "1") (pinfunction "1_1") (pintype "passive"))
      (node (ref "ZD2") (pin "C") (pinfunction "C_C") (pintype "passive"))
    )
    (net (code "184") (name "Net-(SW2-P)") (class "Default")
      (node (ref "C36") (pin "2") (pinfunction "2_2") (pintype "passive"))
      (node (ref "MOD4") (pin "1") (pinfunction "1_1") (pintype "passive"))
      (node (ref "SW2") (pin "2") (pinfunction "P_2") (pintype "passive"))
    )
    (net (code "185") (name "Net-(U7-PALSW)") (class "Default")
      (node (ref "JP1") (pin "1") (pinfunction "1_1") (pintype "passive"))
      (node (ref "U7") (pin "48") (pinfunction "PALSW_48") (pintype "bidirectional"))
    )
    (net (code "186") (name "Net-(U7-PALSW2)") (class "Default")
      (node (ref "JP2") (pin "1") (pinfunction "1_1") (pintype "passive"))
      (node (ref "U7") (pin "34") (pinfunction "PALSW2_34") (pintype "bidirectional"))
    )
    (net (code "187") (name "Net-(U7-~{525}{slash}625)") (class "Default")
      (node (ref "R49") (pin "2") (pinfunction "2_2") (pintype "passive"))
      (node (ref "U7") (pin "13") (pinfunction "~{525}/625_13") (pintype "bidirectional"))
    )
    (net (code "188") (name "Net-(U9A-1A1)") (class "Default")
      (node (ref "J2") (pin "9") (pinfunction "9_9") (pintype "passive"))
      (node (ref "RA1") (pin "2") (pinfunction "2_2") (pintype "passive"))
      (node (ref "U9") (pin "2") (pinfunction "1A1_2") (pintype "input"))
    )
    (net (code "189") (name "Net-(U9A-1A2)") (class "Default")
      (node (ref "J2") (pin "11") (pinfunction "11_11") (pintype "passive"))
      (node (ref "RA1") (pin "4") (pinfunction "4_4") (pintype "passive"))
      (node (ref "U9") (pin "4") (pinfunction "1A2_4") (pintype "input"))
    )
    (net (code "190") (name "Net-(U9A-1A3)") (class "Default")
      (node (ref "J2") (pin "13") (pinfunction "13_13") (pintype "passive"))
      (node (ref "RA1") (pin "6") (pinfunction "6_6") (pintype "passive"))
      (node (ref "U9") (pin "6") (pinfunction "1A3_6") (pintype "input"))
    )
    (net (code "191") (name "Net-(U9A-1A4)") (class "Default")
      (node (ref "J2") (pin "14") (pinfunction "14_14") (pintype "passive"))
      (node (ref "RA1") (pin "7") (pinfunction "7_7") (pintype "passive"))
      (node (ref "U9") (pin "10") (pinfunction "1A4_10") (pintype "input"))
    )
    (net (code "192") (name "Net-(U9A-2A1)") (class "Default")
      (node (ref "J2") (pin "12") (pinfunction "12_12") (pintype "passive"))
      (node (ref "RA1") (pin "5") (pinfunction "5_5") (pintype "passive"))
      (node (ref "U9") (pin "12") (pinfunction "2A1_12") (pintype "input"))
    )
    (net (code "193") (name "Net-(U9A-2A2)") (class "Default")
      (node (ref "J2") (pin "10") (pinfunction "10_10") (pintype "passive"))
      (node (ref "RA1") (pin "3") (pinfunction "3_3") (pintype "passive"))
      (node (ref "U9") (pin "14") (pinfunction "2A2_14") (pintype "input"))
    )
    (net (code "194") (name "Net-(U10-VI)") (class "Default")
      (node (ref "C3") (pin "1") (pinfunction "1_1") (pintype "passive"))
      (node (ref "R46") (pin "2") (pinfunction "2_2") (pintype "passive"))
      (node (ref "SW1") (pin "P$1C") (pinfunction "P$1C_P$1C") (pintype "bidirectional"))
      (node (ref "U10") (pin "1") (pinfunction "VI_1") (pintype "input"))
    )
    (net (code "195") (name "Net-(U11A-I1)") (class "Default")
      (node (ref "C37") (pin "1") (pinfunction "1_1") (pintype "passive"))
      (node (ref "D16") (pin "C") (pinfunction "C_C") (pintype "passive"))
      (node (ref "R55") (pin "2") (pinfunction "2_2") (pintype "passive"))
      (node (ref "U11") (pin "2") (pinfunction "I1_2") (pintype "input"))
    )
    (net (code "196") (name "Net-(U11A-O)") (class "Default")
      (node (ref "JP5") (pin "1") (pinfunction "1_1") (pintype "passive"))
      (node (ref "U11") (pin "12") (pinfunction "O_12") (pintype "output"))
    )
    (net (code "197") (name "Net-(U11B-I0)") (class "Default")
      (node (ref "U11") (pin "3") (pinfunction "I0_3") (pintype "input"))
      (node (ref "U11") (pin "4") (pinfunction "I1_4") (pintype "input"))
    )
    (net (code "198") (name "Net-(U11B-O)") (class "Default")
      (node (ref "U11") (pin "6") (pinfunction "O_6") (pintype "output"))
      (node (ref "U11") (pin "9") (pinfunction "I0_9") (pintype "input"))
    )
    (net (code "199") (name "Net-(U12-Pad13)") (class "Default")
      (node (ref "U12") (pin "13") (pinfunction "13_13") (pintype "passive"))
      (node (ref "XTAL1") (pin "2") (pinfunction "2_2") (pintype "passive"))
    )
    (net (code "200") (name "Net-(U13A-I)") (class "Default")
      (node (ref "C23") (pin "1") (pinfunction "1_1") (pintype "passive"))
      (node (ref "R50") (pin "2") (pinfunction "2_2") (pintype "passive"))
      (node (ref "U13") (pin "1") (pinfunction "I_1") (pintype "input"))
    )
    (net (code "201") (name "Net-(U13A-O)") (class "Default")
      (node (ref "R50") (pin "1") (pinfunction "1_1") (pintype "passive"))
      (node (ref "R51") (pin "1") (pinfunction "1_1") (pintype "passive"))
      (node (ref "U13") (pin "2") (pinfunction "O_2") (pintype "output"))
      (node (ref "U13") (pin "3") (pinfunction "I_3") (pintype "input"))
    )
    (net (code "202") (name "Net-(U13B-O)") (class "Default")
      (node (ref "R51") (pin "2") (pinfunction "2_2") (pintype "passive"))
      (node (ref "U13") (pin "4") (pinfunction "O_4") (pintype "output"))
      (node (ref "U13") (pin "5") (pinfunction "I_5") (pintype "input"))
      (node (ref "XTAL2") (pin "1") (pinfunction "1_1") (pintype "passive"))
    )
    (net (code "203") (name "Net-(U13C-O)") (class "Default")
      (node (ref "R52") (pin "2") (pinfunction "2_2") (pintype "passive"))
      (node (ref "U13") (pin "6") (pinfunction "O_6") (pintype "output"))
    )
    (net (code "204") (name "Net-(U14A-Q)") (class "Default")
      (node (ref "U14") (pin "6") (pinfunction "Q_6") (pintype "output"))
      (node (ref "U16") (pin "12") (pinfunction "C_12") (pintype "input"))
    )
    (net (code "205") (name "Net-(U14A-T2)") (class "Default")
      (node (ref "C33") (pin "2") (pinfunction "2_2") (pintype "passive"))
      (node (ref "R58") (pin "1") (pinfunction "1_1") (pintype "passive"))
      (node (ref "U14") (pin "2") (pinfunction "T2_2") (pintype "input"))
    )
    (net (code "206") (name "Net-(U14A-~{Q})") (class "Default")
      (node (ref "U14") (pin "7") (pinfunction "~{Q}_7") (pintype "output"))
      (node (ref "U16") (pin "13") (pinfunction "C_13") (pintype "input"))
    )
    (net (code "207") (name "Net-(U16D-B)") (class "Default")
      (node (ref "C39") (pin "2") (pinfunction "2_2") (pintype "passive"))
      (node (ref "R59") (pin "1") (pinfunction "1_1") (pintype "passive"))
      (node (ref "U16") (pin "10") (pinfunction "B_10") (pintype "passive"))
    )
    (net (code "208") (name "PIN-8.8VDC") (class "Default")
      (node (ref "C40") (pin "1") (pinfunction "1_1") (pintype "passive"))
      (node (ref "J3") (pin "3") (pinfunction "3_3") (pintype "bidirectional"))
      (node (ref "L6") (pin "1") (pinfunction "1_1") (pintype "passive"))
    )
    (net (code "209") (name "PIN-16VDC") (class "Default")
      (node (ref "C42") (pin "1") (pinfunction "1_1") (pintype "passive"))
      (node (ref "J3") (pin "4") (pinfunction "4_4") (pintype "bidirectional"))
      (node (ref "L5") (pin "1") (pinfunction "1_1") (pintype "passive"))
    )
    (net (code "210") (name "PIN-19VDC") (class "Default")
      (node (ref "C41") (pin "1") (pinfunction "1_1") (pintype "passive"))
      (node (ref "J3") (pin "1") (pinfunction "1_1") (pintype "bidirectional"))
      (node (ref "L8") (pin "1") (pinfunction "1_1") (pintype "passive"))
    )
    (net (code "211") (name "PIN-GND") (class "Default")
      (node (ref "J3") (pin "2") (pinfunction "2_2") (pintype "bidirectional"))
      (node (ref "L7") (pin "1") (pinfunction "1_1") (pintype "passive"))
    )
    (net (code "212") (name "SND") (class "Default")
      (node (ref "J1") (pin "P$2") (pinfunction "X2_P$2") (pintype "bidirectional"))
      (node (ref "MOD3") (pin "1") (pinfunction "1_1") (pintype "passive"))
      (node (ref "R43") (pin "2") (pinfunction "2_2") (pintype "passive"))
      (node (ref "R47") (pin "1") (pinfunction "1_1") (pintype "passive"))
    )
    (net (code "213") (name "VCC") (class "Default")
      (node (ref "C10") (pin "2") (pinfunction "2_2") (pintype "passive"))
      (node (ref "C17") (pin "1") (pinfunction "1_1") (pintype "passive"))
      (node (ref "C20") (pin "1") (pinfunction "1_1") (pintype "passive"))
      (node (ref "C21") (pin "1") (pinfunction "1_1") (pintype "passive"))
      (node (ref "C22") (pin "1") (pinfunction "1_1") (pintype "passive"))
      (node (ref "C24") (pin "1") (pinfunction "1_1") (pintype "passive"))
      (node (ref "C25") (pin "1") (pinfunction "1_1") (pintype "passive"))
      (node (ref "C26") (pin "1") (pinfunction "1_1") (pintype "passive"))
      (node (ref "C27") (pin "1") (pinfunction "1_1") (pintype "passive"))
      (node (ref "C28") (pin "2") (pinfunction "2_2") (pintype "passive"))
      (node (ref "C35") (pin "1") (pinfunction "1_1") (pintype "passive"))
      (node (ref "C43") (pin "1") (pinfunction "1_1") (pintype "passive"))
      (node (ref "C6") (pin "+") (pinfunction "+_+") (pintype "passive"))
      (node (ref "D1") (pin "C") (pinfunction "C_C") (pintype "passive"))
      (node (ref "D14") (pin "A") (pinfunction "A_A") (pintype "passive"))
      (node (ref "J1") (pin "P$25") (pinfunction "X25_P$25") (pintype "bidirectional"))
      (node (ref "JP4") (pin "1") (pinfunction "1_1") (pintype "passive"))
      (node (ref "R1") (pin "2") (pinfunction "2_2") (pintype "passive"))
      (node (ref "R14") (pin "1") (pinfunction "1_1") (pintype "passive"))
      (node (ref "R17") (pin "1") (pinfunction "1_1") (pintype "passive"))
      (node (ref "R18") (pin "1") (pinfunction "1_1") (pintype "passive"))
      (node (ref "R19") (pin "1") (pinfunction "1_1") (pintype "passive"))
      (node (ref "R2") (pin "2") (pinfunction "2_2") (pintype "passive"))
      (node (ref "R21") (pin "1") (pinfunction "1_1") (pintype "passive"))
      (node (ref "R25") (pin "2") (pinfunction "2_2") (pintype "passive"))
      (node (ref "R3") (pin "2") (pinfunction "2_2") (pintype "passive"))
      (node (ref "R4") (pin "1") (pinfunction "1_1") (pintype "passive"))
      (node (ref "R49") (pin "1") (pinfunction "1_1") (pintype "passive"))
      (node (ref "R5") (pin "2") (pinfunction "2_2") (pintype "passive"))
      (node (ref "R58") (pin "2") (pinfunction "2_2") (pintype "passive"))
      (node (ref "RA1") (pin "1") (pinfunction "1_1") (pintype "passive"))
      (node (ref "U1") (pin "11") (pinfunction "VCC_11") (pintype "power_in"))
      (node (ref "U10") (pin "3") (pinfunction "VO_3") (pintype "passive"))
      (node (ref "U11") (pin "1") (pinfunction "I0_1") (pintype "input"))
      (node (ref "U11") (pin "13") (pinfunction "I2_13") (pintype "input"))
      (node (ref "U14") (pin "3") (pinfunction "CD_3") (pintype "input"))
      (node (ref "U14") (pin "5") (pinfunction "B_5") (pintype "input"))
      (node (ref "U2") (pin "24") (pinfunction "24_24") (pintype "passive"))
      (node (ref "U5") (pin "21") (pinfunction "21_21") (pintype "passive"))
      (node (ref "U5") (pin "24") (pinfunction "24_24") (pintype "passive"))
      (node (ref "U7") (pin "12") (pinfunction "P12_12") (pintype "bidirectional"))
      (node (ref "U7") (pin "32") (pinfunction "P32_32") (pintype "bidirectional"))
      (node (ref "U7") (pin "64") (pinfunction "+5V_64") (pintype "power_in"))
      (node (ref "U8") (pin "35") (pinfunction "35_35") (pintype "passive"))
    )
    (net (code "214") (name "VEE") (class "Default")
      (node (ref "JP4") (pin "3") (pinfunction "3_3") (pintype "passive"))
      (node (ref "R28") (pin "2") (pinfunction "2_2") (pintype "passive"))
      (node (ref "SW1") (pin "P$3C") (pinfunction "P$3C_P$3C") (pintype "bidirectional"))
    )
    (net (code "215") (name "VPP") (class "Default")
      (node (ref "C12") (pin "+") (pinfunction "+_+") (pintype "passive"))
      (node (ref "C15") (pin "1") (pinfunction "1_1") (pintype "passive"))
      (node (ref "C32") (pin "1") (pinfunction "1_1") (pintype "passive"))
      (node (ref "JP4") (pin "2") (pinfunction "2_2") (pintype "passive"))
      (node (ref "L-V1") (pin "P$2") (pinfunction "P$2_P$2") (pintype "bidirectional"))
      (node (ref "L-V1") (pin "P$4") (pinfunction "P$2_P$4") (pintype "bidirectional"))
      (node (ref "Q3") (pin "3") (pinfunction "E_3") (pintype "passive"))
      (node (ref "Q4") (pin "3") (pinfunction "E_3") (pintype "passive"))
      (node (ref "Q7") (pin "1") (pinfunction "C_1") (pintype "passive"))
      (node (ref "R26") (pin "1") (pinfunction "1_1") (pintype "passive"))
      (node (ref "R27") (pin "2") (pinfunction "2_2") (pintype "passive"))
      (node (ref "R40") (pin "2") (pinfunction "2_2") (pintype "passive"))
      (node (ref "R47") (pin "2") (pinfunction "2_2") (pintype "passive"))
      (node (ref "R54") (pin "1") (pinfunction "1_1") (pintype "passive"))
      (node (ref "R57") (pin "2") (pinfunction "2_2") (pintype "passive"))
      (node (ref "R60") (pin "2") (pinfunction "2_2") (pintype "passive"))
      (node (ref "U12") (pin "10") (pinfunction "10_10") (pintype "passive"))
    )
    (net (code "216") (name "unconnected-(J5-Pad4)") (class "Default")
      (node (ref "J5") (pin "4") (pinfunction "4_4") (pintype "bidirectional"))
    )
    (net (code "217") (name "unconnected-(J5-Pad5)") (class "Default")
      (node (ref "J5") (pin "5") (pinfunction "5_5") (pintype "bidirectional"))
    )
    (net (code "218") (name "unconnected-(SW2-S-Pad1)") (class "Default")
      (node (ref "SW2") (pin "1") (pinfunction "S_1") (pintype "passive"))
    )
    (net (code "219") (name "unconnected-(U6A-~{QH}-Pad7)") (class "Default")
      (node (ref "U6") (pin "7") (pinfunction "~{QH}_7") (pintype "output"))
    )
    (net (code "220") (name "unconnected-(U8-Pad7)") (class "Default")
      (node (ref "U8") (pin "7") (pinfunction "7_7") (pintype "passive"))
    )
    (net (code "221") (name "unconnected-(U8-Pad8)") (class "Default")
      (node (ref "U8") (pin "8") (pinfunction "8_8") (pintype "passive"))
    )
    (net (code "222") (name "Φ") (class "Default")
      (node (ref "J1") (pin "P$8") (pinfunction "X8_P$8") (pintype "bidirectional"))
      (node (ref "U1") (pin "6") (pinfunction "CLK_6") (pintype "input"))
      (node (ref "U7") (pin "31") (pinfunction "Φ_31") (pintype "bidirectional"))
    )
  )
)
